# coronaampel_v2_fixed.net
KiCad netlist of a schematic drawn in EAGLE
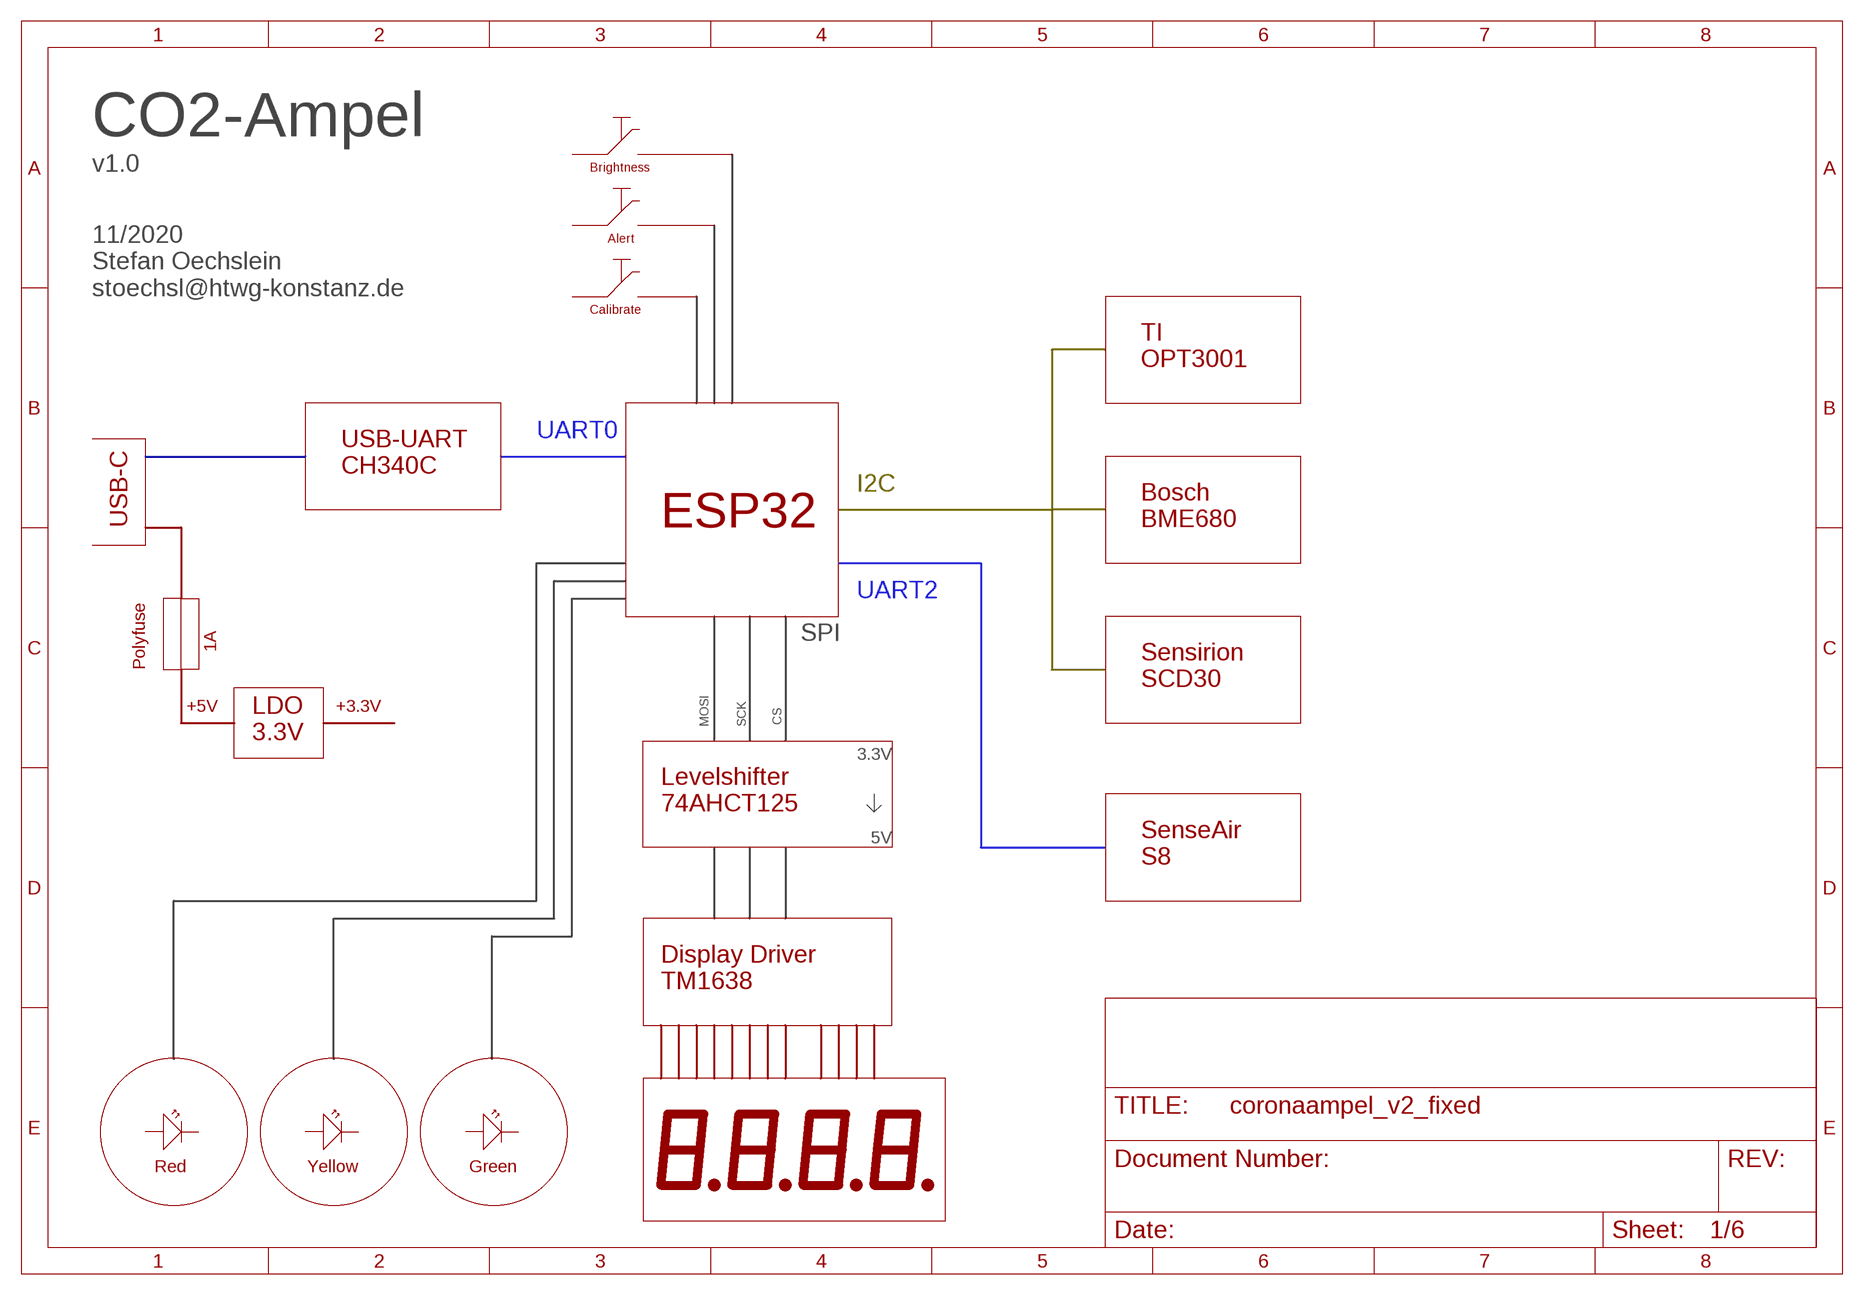
[diagram p0: schematic, sheet 1]
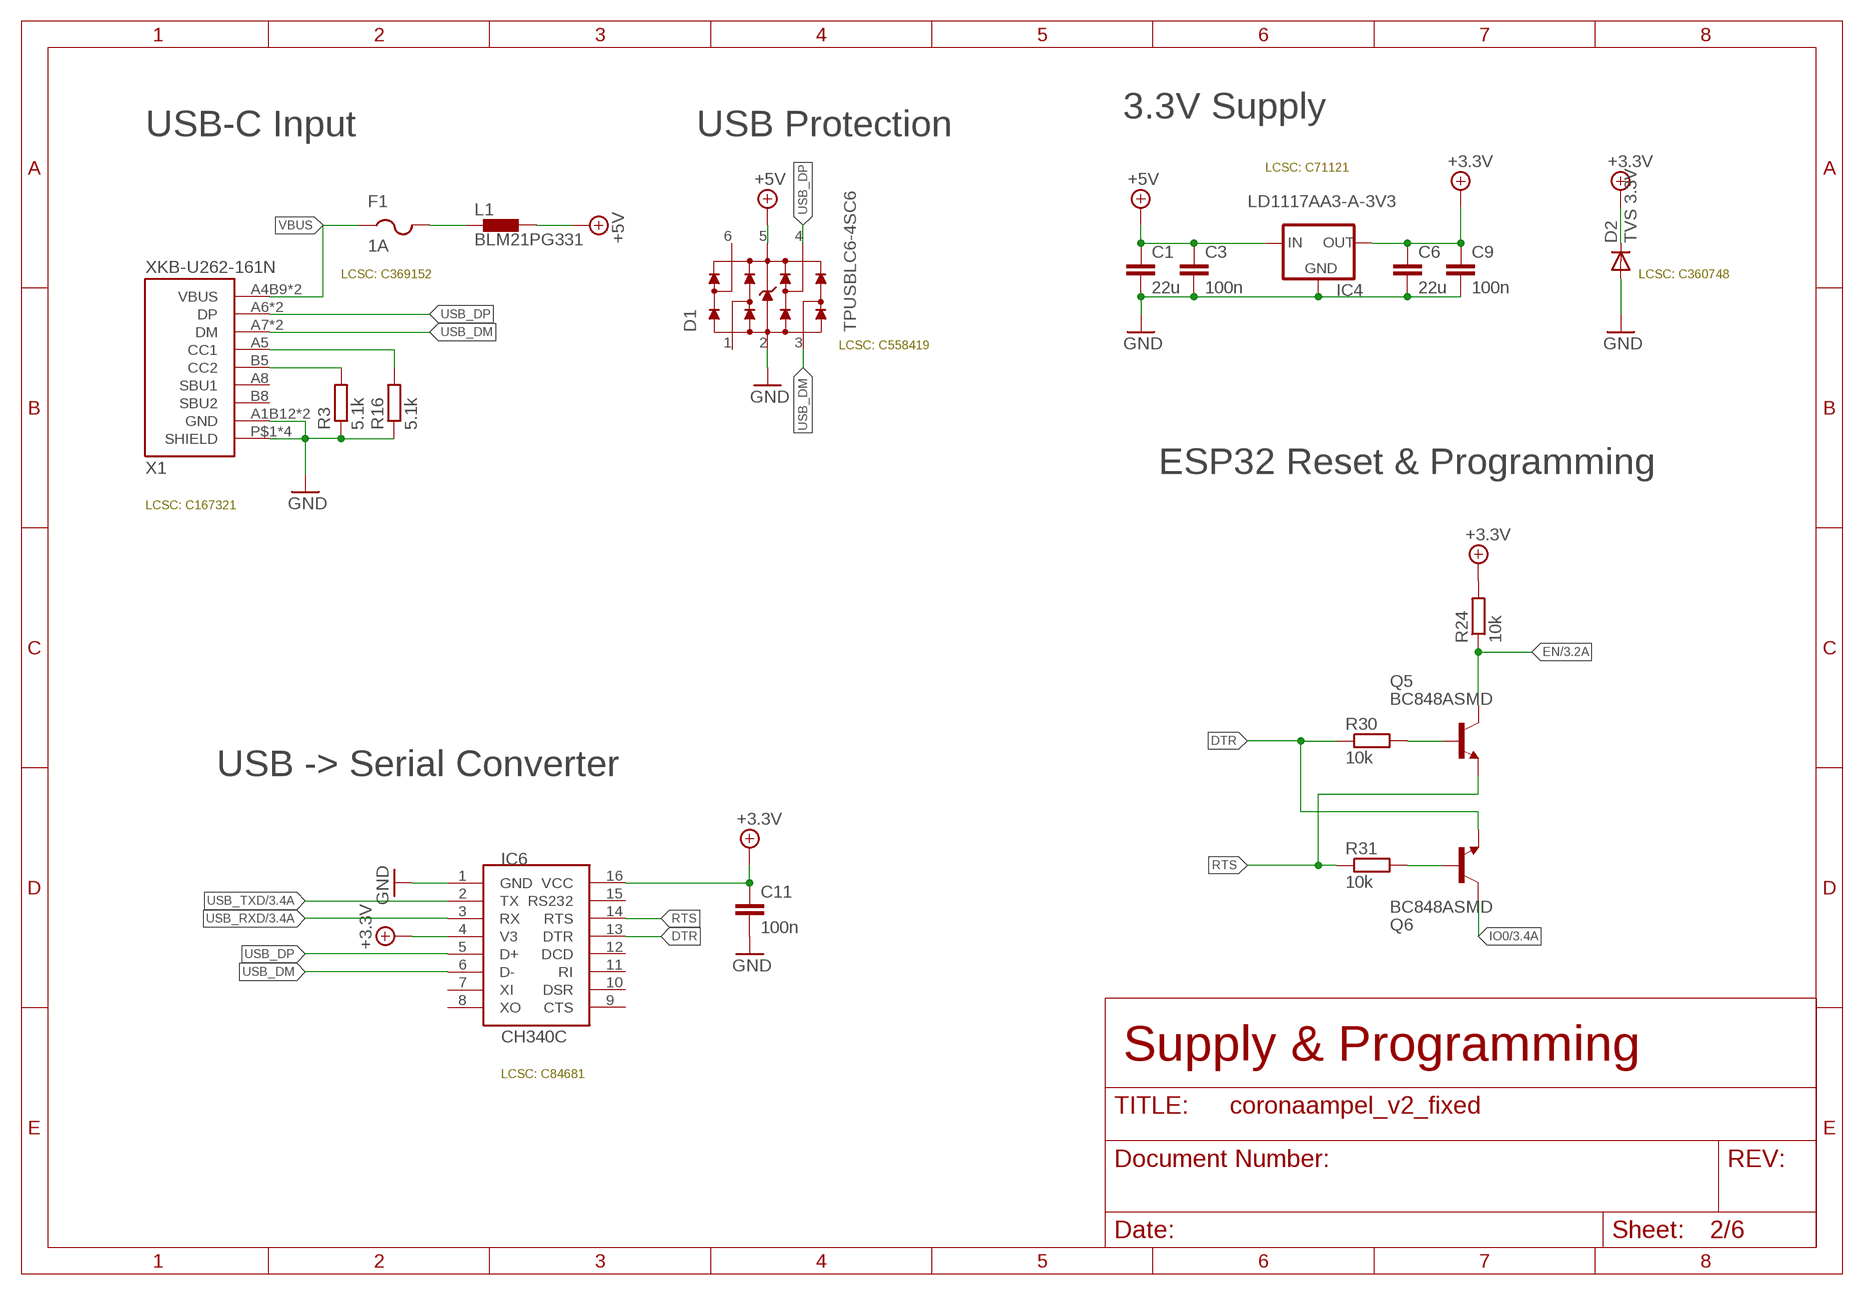
[diagram p1: schematic, sheet 2]
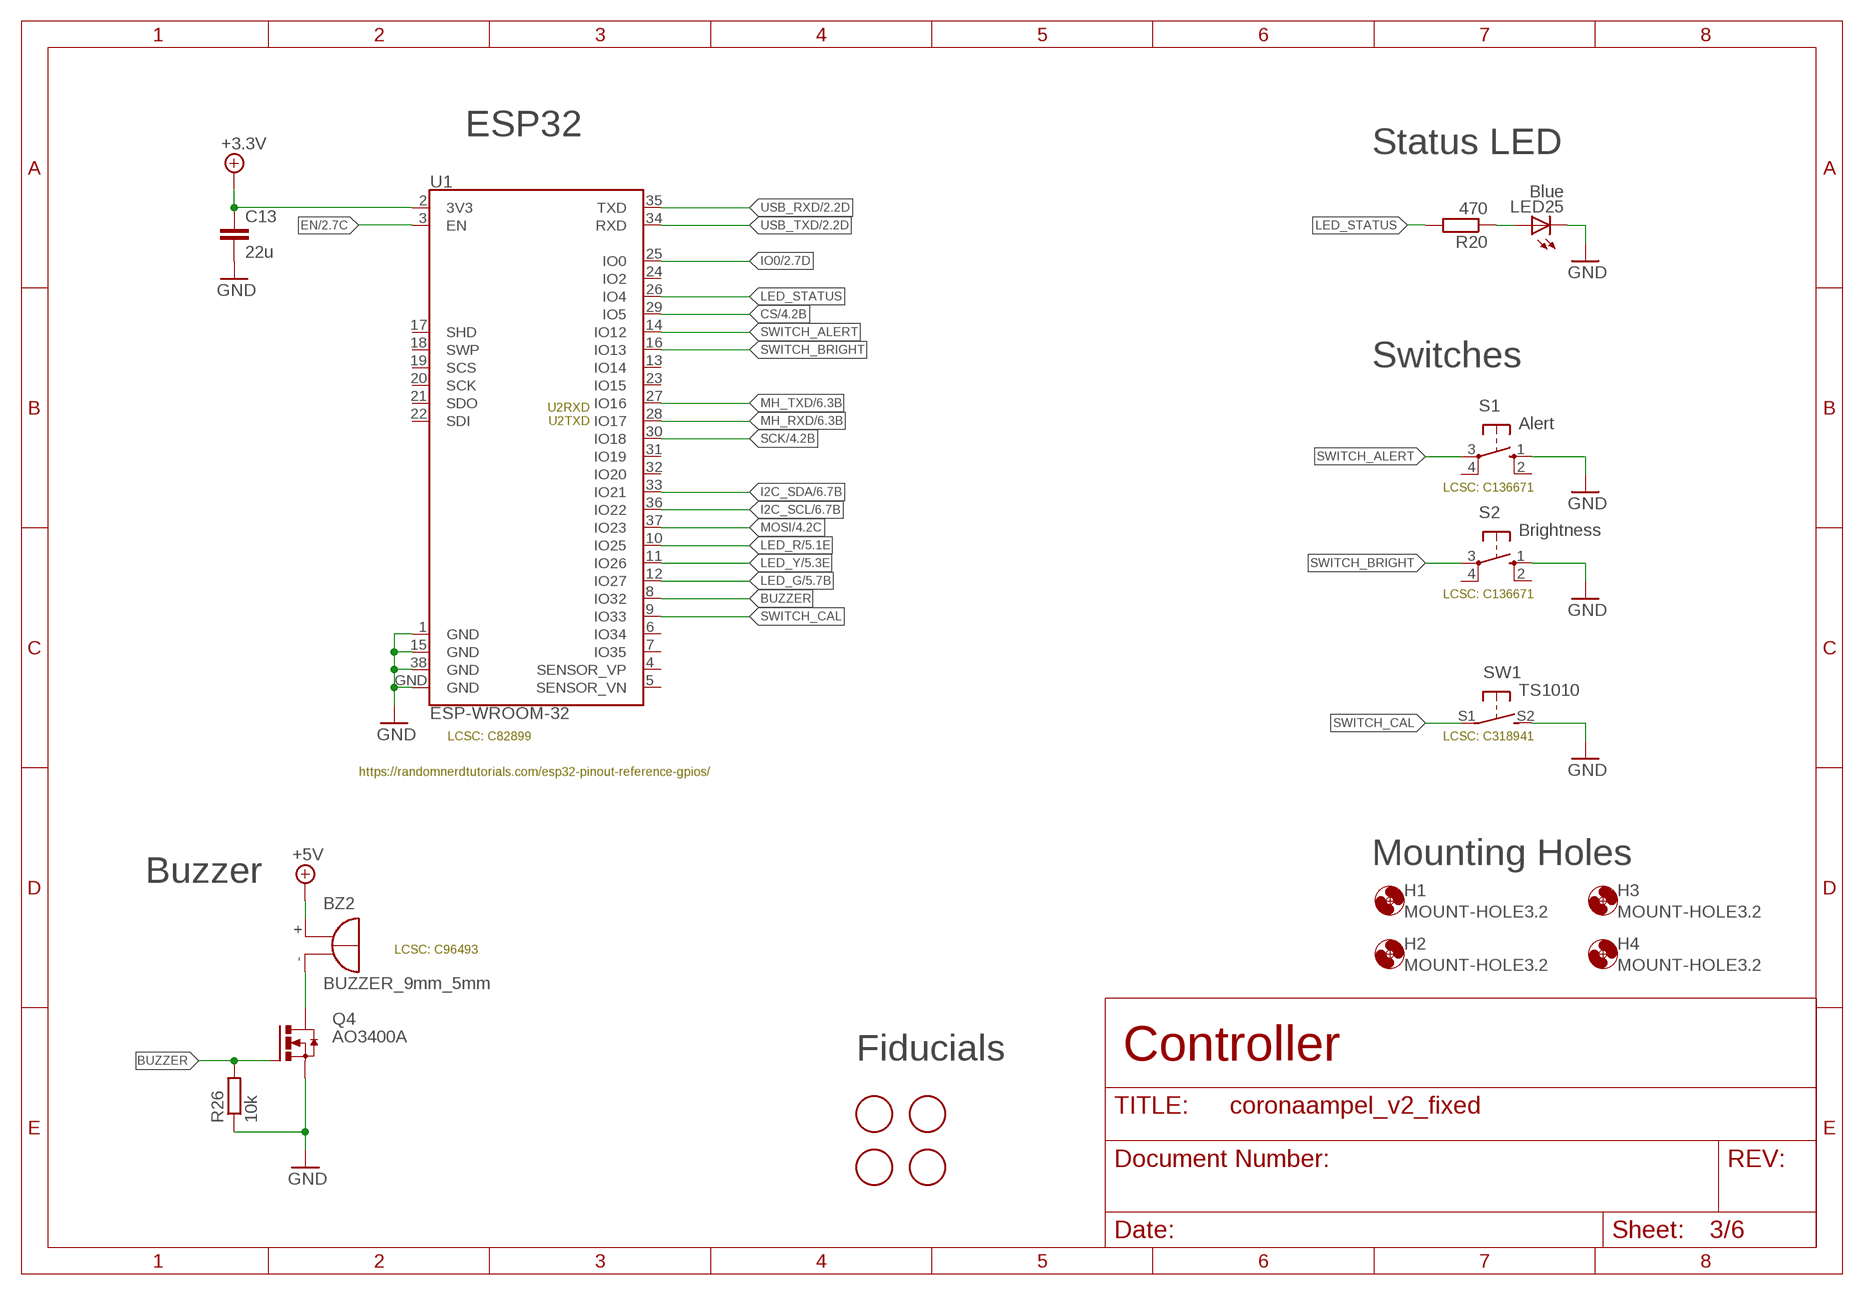
[diagram p2: schematic, sheet 3]
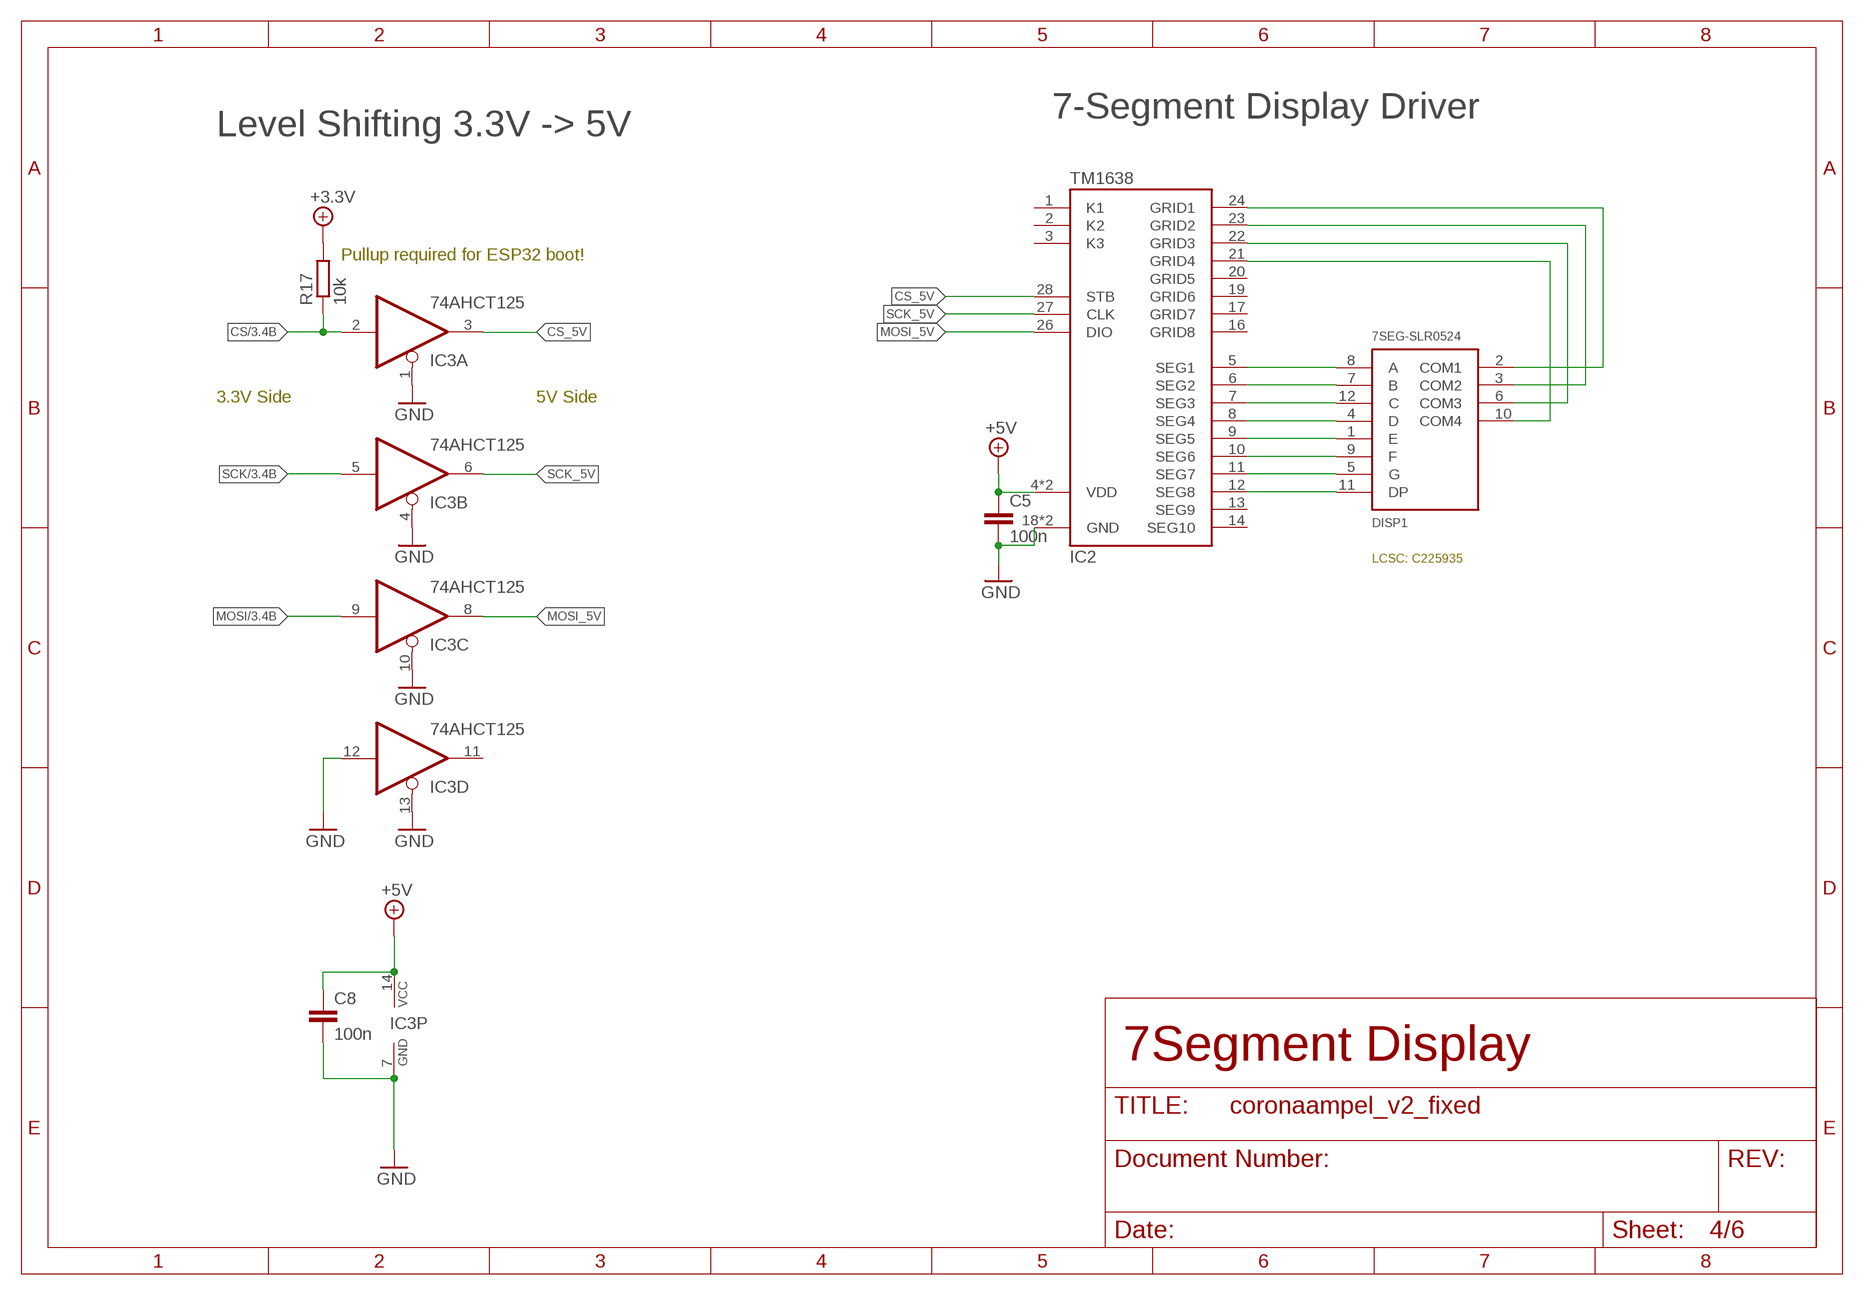
[diagram p3: schematic, sheet 4]
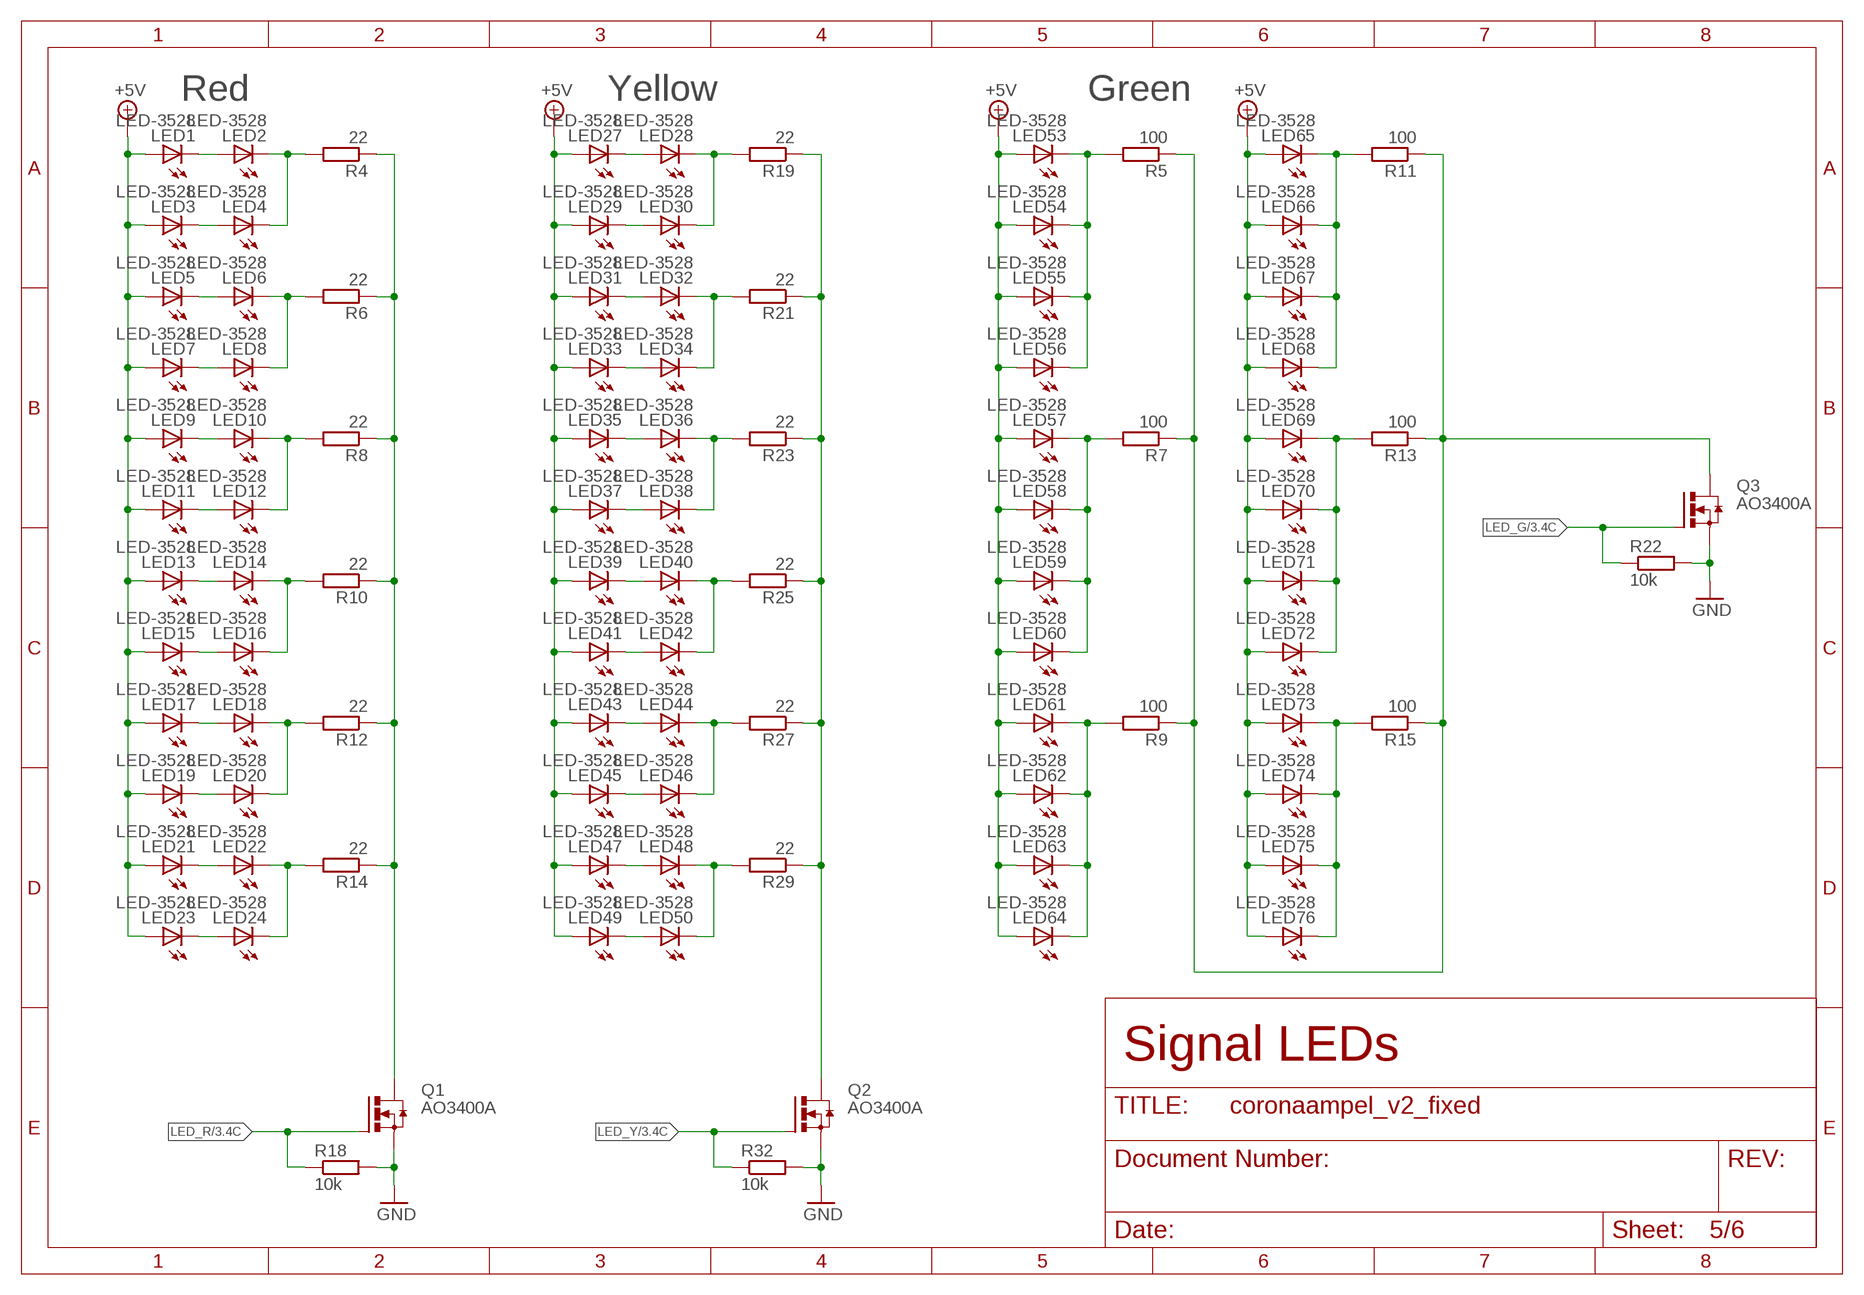
[diagram p4: schematic, sheet 5]
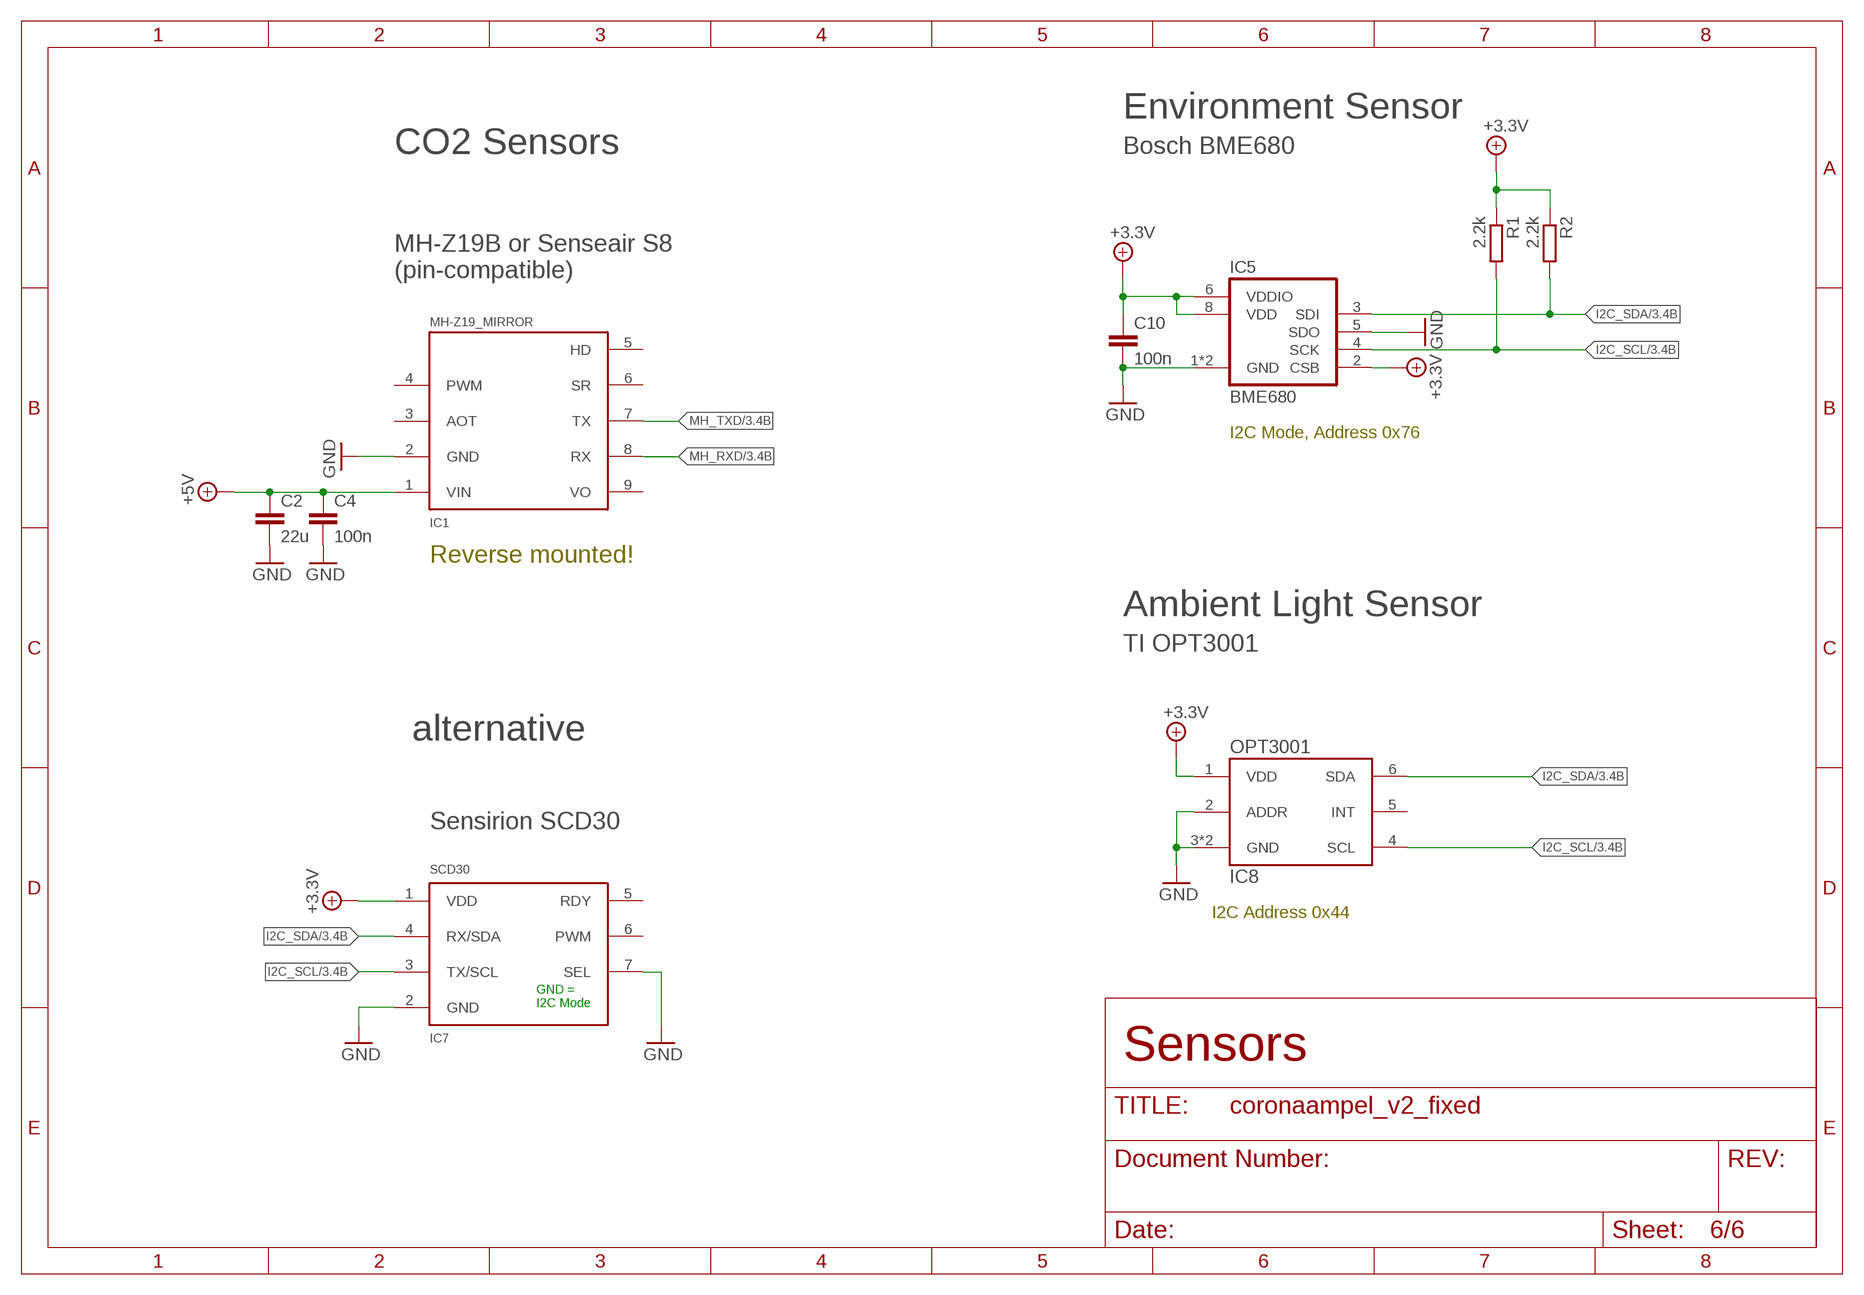
[diagram p5: schematic, sheet 6]

(export (version "E")
  (design (tool "Eeschema 10.0.6"))
  (components
    (comp (ref "C1")
      (value "22u")
      (footprint "eagle-import:C0805")
      (libsource (lib "eagle-import") (part "C-EUC0805"))
    )
    (comp (ref "C3")
      (value "100n")
      (footprint "eagle-import:C0805")
      (libsource (lib "eagle-import") (part "C-EUC0805"))
    )
    (comp (ref "C6")
      (value "22u")
      (footprint "eagle-import:C0805")
      (libsource (lib "eagle-import") (part "C-EUC0805"))
    )
    (comp (ref "C9")
      (value "100n")
      (footprint "eagle-import:C0805")
      (libsource (lib "eagle-import") (part "C-EUC0805"))
    )
    (comp (ref "C11")
      (value "100n")
      (footprint "eagle-import:C0805")
      (libsource (lib "eagle-import") (part "C-EUC0805"))
    )
    (comp (ref "D1")
      (value "TPUSBLC6-4SC6")
      (footprint "eagle-import:WE-TVS_SOT23-6L")
      (libsource (lib "eagle-import") (part "WE-TVS_824001"))
    )
    (comp (ref "D2")
      (value "TVS 3.3V")
      (footprint "eagle-import:SOD123")
      (libsource (lib "eagle-import") (part "DIODE-SOD123"))
    )
    (comp (ref "F1")
      (value "1A")
      (footprint "eagle-import:R0805")
      (libsource (lib "eagle-import") (part "PTCFUSE-0805"))
    )
    (comp (ref "IC4")
      (value "LD1117AA3-A-3V3")
      (footprint "eagle-import:SOT223")
      (libsource (lib "eagle-import") (part "LD1117AA3-A"))
    )
    (comp (ref "IC6")
      (value "CH340C")
      (footprint "eagle-import:SOIC16")
      (libsource (lib "eagle-import") (part "CH340G"))
    )
    (comp (ref "L1")
      (value "BLM21PG331")
      (footprint "eagle-import:0805")
      (libsource (lib "eagle-import") (part "BLM21PG331"))
    )
    (comp (ref "Q5")
      (value "BC848ASMD")
      (footprint "eagle-import:SOT23")
      (libsource (lib "eagle-import") (part "BC848SMDA"))
    )
    (comp (ref "Q6")
      (value "BC848ASMD")
      (footprint "eagle-import:SOT23")
      (libsource (lib "eagle-import") (part "BC848SMDA"))
    )
    (comp (ref "R3")
      (value "5.1k")
      (footprint "eagle-import:R0805")
      (libsource (lib "eagle-import") (part "R-EU_R0805"))
    )
    (comp (ref "R16")
      (value "5.1k")
      (footprint "eagle-import:R0805")
      (libsource (lib "eagle-import") (part "R-EU_R0805"))
    )
    (comp (ref "R24")
      (value "10k")
      (footprint "eagle-import:R0805")
      (libsource (lib "eagle-import") (part "R-EU_R0805"))
    )
    (comp (ref "R30")
      (value "10k")
      (footprint "eagle-import:R0805")
      (libsource (lib "eagle-import") (part "R-EU_R0805"))
    )
    (comp (ref "R31")
      (value "10k")
      (footprint "eagle-import:R0805")
      (libsource (lib "eagle-import") (part "R-EU_R0805"))
    )
    (comp (ref "X1")
      (value "XKB-U262-161N")
      (footprint "eagle-import:XKB_U262-161N")
      (libsource (lib "eagle-import") (part "XKB-U262-161N"))
    )
    (comp (ref "LED1")
      (value "LED-3528")
      (footprint "eagle-import:3528")
      (libsource (lib "eagle-import") (part "LED-3528"))
    )
    (comp (ref "LED2")
      (value "LED-3528")
      (footprint "eagle-import:3528")
      (libsource (lib "eagle-import") (part "LED-3528"))
    )
    (comp (ref "LED3")
      (value "LED-3528")
      (footprint "eagle-import:3528")
      (libsource (lib "eagle-import") (part "LED-3528"))
    )
    (comp (ref "LED4")
      (value "LED-3528")
      (footprint "eagle-import:3528")
      (libsource (lib "eagle-import") (part "LED-3528"))
    )
    (comp (ref "LED5")
      (value "LED-3528")
      (footprint "eagle-import:3528")
      (libsource (lib "eagle-import") (part "LED-3528"))
    )
    (comp (ref "LED6")
      (value "LED-3528")
      (footprint "eagle-import:3528")
      (libsource (lib "eagle-import") (part "LED-3528"))
    )
    (comp (ref "LED7")
      (value "LED-3528")
      (footprint "eagle-import:3528")
      (libsource (lib "eagle-import") (part "LED-3528"))
    )
    (comp (ref "LED8")
      (value "LED-3528")
      (footprint "eagle-import:3528")
      (libsource (lib "eagle-import") (part "LED-3528"))
    )
    (comp (ref "LED9")
      (value "LED-3528")
      (footprint "eagle-import:3528")
      (libsource (lib "eagle-import") (part "LED-3528"))
    )
    (comp (ref "LED10")
      (value "LED-3528")
      (footprint "eagle-import:3528")
      (libsource (lib "eagle-import") (part "LED-3528"))
    )
    (comp (ref "LED11")
      (value "LED-3528")
      (footprint "eagle-import:3528")
      (libsource (lib "eagle-import") (part "LED-3528"))
    )
    (comp (ref "LED12")
      (value "LED-3528")
      (footprint "eagle-import:3528")
      (libsource (lib "eagle-import") (part "LED-3528"))
    )
    (comp (ref "LED13")
      (value "LED-3528")
      (footprint "eagle-import:3528")
      (libsource (lib "eagle-import") (part "LED-3528"))
    )
    (comp (ref "LED14")
      (value "LED-3528")
      (footprint "eagle-import:3528")
      (libsource (lib "eagle-import") (part "LED-3528"))
    )
    (comp (ref "LED15")
      (value "LED-3528")
      (footprint "eagle-import:3528")
      (libsource (lib "eagle-import") (part "LED-3528"))
    )
    (comp (ref "LED16")
      (value "LED-3528")
      (footprint "eagle-import:3528")
      (libsource (lib "eagle-import") (part "LED-3528"))
    )
    (comp (ref "LED17")
      (value "LED-3528")
      (footprint "eagle-import:3528")
      (libsource (lib "eagle-import") (part "LED-3528"))
    )
    (comp (ref "LED18")
      (value "LED-3528")
      (footprint "eagle-import:3528")
      (libsource (lib "eagle-import") (part "LED-3528"))
    )
    (comp (ref "LED19")
      (value "LED-3528")
      (footprint "eagle-import:3528")
      (libsource (lib "eagle-import") (part "LED-3528"))
    )
    (comp (ref "LED20")
      (value "LED-3528")
      (footprint "eagle-import:3528")
      (libsource (lib "eagle-import") (part "LED-3528"))
    )
    (comp (ref "LED21")
      (value "LED-3528")
      (footprint "eagle-import:3528")
      (libsource (lib "eagle-import") (part "LED-3528"))
    )
    (comp (ref "LED22")
      (value "LED-3528")
      (footprint "eagle-import:3528")
      (libsource (lib "eagle-import") (part "LED-3528"))
    )
    (comp (ref "LED23")
      (value "LED-3528")
      (footprint "eagle-import:3528")
      (libsource (lib "eagle-import") (part "LED-3528"))
    )
    (comp (ref "LED24")
      (value "LED-3528")
      (footprint "eagle-import:3528")
      (libsource (lib "eagle-import") (part "LED-3528"))
    )
    (comp (ref "LED27")
      (value "LED-3528")
      (footprint "eagle-import:3528")
      (libsource (lib "eagle-import") (part "LED-3528"))
    )
    (comp (ref "LED28")
      (value "LED-3528")
      (footprint "eagle-import:3528")
      (libsource (lib "eagle-import") (part "LED-3528"))
    )
    (comp (ref "LED29")
      (value "LED-3528")
      (footprint "eagle-import:3528")
      (libsource (lib "eagle-import") (part "LED-3528"))
    )
    (comp (ref "LED30")
      (value "LED-3528")
      (footprint "eagle-import:3528")
      (libsource (lib "eagle-import") (part "LED-3528"))
    )
    (comp (ref "LED31")
      (value "LED-3528")
      (footprint "eagle-import:3528")
      (libsource (lib "eagle-import") (part "LED-3528"))
    )
    (comp (ref "LED32")
      (value "LED-3528")
      (footprint "eagle-import:3528")
      (libsource (lib "eagle-import") (part "LED-3528"))
    )
    (comp (ref "LED33")
      (value "LED-3528")
      (footprint "eagle-import:3528")
      (libsource (lib "eagle-import") (part "LED-3528"))
    )
    (comp (ref "LED34")
      (value "LED-3528")
      (footprint "eagle-import:3528")
      (libsource (lib "eagle-import") (part "LED-3528"))
    )
    (comp (ref "LED35")
      (value "LED-3528")
      (footprint "eagle-import:3528")
      (libsource (lib "eagle-import") (part "LED-3528"))
    )
    (comp (ref "LED36")
      (value "LED-3528")
      (footprint "eagle-import:3528")
      (libsource (lib "eagle-import") (part "LED-3528"))
    )
    (comp (ref "LED37")
      (value "LED-3528")
      (footprint "eagle-import:3528")
      (libsource (lib "eagle-import") (part "LED-3528"))
    )
    (comp (ref "LED38")
      (value "LED-3528")
      (footprint "eagle-import:3528")
      (libsource (lib "eagle-import") (part "LED-3528"))
    )
    (comp (ref "LED39")
      (value "LED-3528")
      (footprint "eagle-import:3528")
      (libsource (lib "eagle-import") (part "LED-3528"))
    )
    (comp (ref "LED40")
      (value "LED-3528")
      (footprint "eagle-import:3528")
      (libsource (lib "eagle-import") (part "LED-3528"))
    )
    (comp (ref "LED41")
      (value "LED-3528")
      (footprint "eagle-import:3528")
      (libsource (lib "eagle-import") (part "LED-3528"))
    )
    (comp (ref "LED42")
      (value "LED-3528")
      (footprint "eagle-import:3528")
      (libsource (lib "eagle-import") (part "LED-3528"))
    )
    (comp (ref "LED43")
      (value "LED-3528")
      (footprint "eagle-import:3528")
      (libsource (lib "eagle-import") (part "LED-3528"))
    )
    (comp (ref "LED44")
      (value "LED-3528")
      (footprint "eagle-import:3528")
      (libsource (lib "eagle-import") (part "LED-3528"))
    )
    (comp (ref "LED45")
      (value "LED-3528")
      (footprint "eagle-import:3528")
      (libsource (lib "eagle-import") (part "LED-3528"))
    )
    (comp (ref "LED46")
      (value "LED-3528")
      (footprint "eagle-import:3528")
      (libsource (lib "eagle-import") (part "LED-3528"))
    )
    (comp (ref "LED47")
      (value "LED-3528")
      (footprint "eagle-import:3528")
      (libsource (lib "eagle-import") (part "LED-3528"))
    )
    (comp (ref "LED48")
      (value "LED-3528")
      (footprint "eagle-import:3528")
      (libsource (lib "eagle-import") (part "LED-3528"))
    )
    (comp (ref "LED49")
      (value "LED-3528")
      (footprint "eagle-import:3528")
      (libsource (lib "eagle-import") (part "LED-3528"))
    )
    (comp (ref "LED50")
      (value "LED-3528")
      (footprint "eagle-import:3528")
      (libsource (lib "eagle-import") (part "LED-3528"))
    )
    (comp (ref "LED53")
      (value "LED-3528")
      (footprint "eagle-import:3528")
      (libsource (lib "eagle-import") (part "LED-3528"))
    )
    (comp (ref "LED54")
      (value "LED-3528")
      (footprint "eagle-import:3528")
      (libsource (lib "eagle-import") (part "LED-3528"))
    )
    (comp (ref "LED55")
      (value "LED-3528")
      (footprint "eagle-import:3528")
      (libsource (lib "eagle-import") (part "LED-3528"))
    )
    (comp (ref "LED56")
      (value "LED-3528")
      (footprint "eagle-import:3528")
      (libsource (lib "eagle-import") (part "LED-3528"))
    )
    (comp (ref "LED57")
      (value "LED-3528")
      (footprint "eagle-import:3528")
      (libsource (lib "eagle-import") (part "LED-3528"))
    )
    (comp (ref "LED58")
      (value "LED-3528")
      (footprint "eagle-import:3528")
      (libsource (lib "eagle-import") (part "LED-3528"))
    )
    (comp (ref "LED59")
      (value "LED-3528")
      (footprint "eagle-import:3528")
      (libsource (lib "eagle-import") (part "LED-3528"))
    )
    (comp (ref "LED60")
      (value "LED-3528")
      (footprint "eagle-import:3528")
      (libsource (lib "eagle-import") (part "LED-3528"))
    )
    (comp (ref "LED61")
      (value "LED-3528")
      (footprint "eagle-import:3528")
      (libsource (lib "eagle-import") (part "LED-3528"))
    )
    (comp (ref "LED62")
      (value "LED-3528")
      (footprint "eagle-import:3528")
      (libsource (lib "eagle-import") (part "LED-3528"))
    )
    (comp (ref "LED63")
      (value "LED-3528")
      (footprint "eagle-import:3528")
      (libsource (lib "eagle-import") (part "LED-3528"))
    )
    (comp (ref "LED64")
      (value "LED-3528")
      (footprint "eagle-import:3528")
      (libsource (lib "eagle-import") (part "LED-3528"))
    )
    (comp (ref "LED65")
      (value "LED-3528")
      (footprint "eagle-import:3528")
      (libsource (lib "eagle-import") (part "LED-3528"))
    )
    (comp (ref "LED66")
      (value "LED-3528")
      (footprint "eagle-import:3528")
      (libsource (lib "eagle-import") (part "LED-3528"))
    )
    (comp (ref "LED67")
      (value "LED-3528")
      (footprint "eagle-import:3528")
      (libsource (lib "eagle-import") (part "LED-3528"))
    )
    (comp (ref "LED68")
      (value "LED-3528")
      (footprint "eagle-import:3528")
      (libsource (lib "eagle-import") (part "LED-3528"))
    )
    (comp (ref "LED69")
      (value "LED-3528")
      (footprint "eagle-import:3528")
      (libsource (lib "eagle-import") (part "LED-3528"))
    )
    (comp (ref "LED70")
      (value "LED-3528")
      (footprint "eagle-import:3528")
      (libsource (lib "eagle-import") (part "LED-3528"))
    )
    (comp (ref "LED71")
      (value "LED-3528")
      (footprint "eagle-import:3528")
      (libsource (lib "eagle-import") (part "LED-3528"))
    )
    (comp (ref "LED72")
      (value "LED-3528")
      (footprint "eagle-import:3528")
      (libsource (lib "eagle-import") (part "LED-3528"))
    )
    (comp (ref "LED73")
      (value "LED-3528")
      (footprint "eagle-import:3528")
      (libsource (lib "eagle-import") (part "LED-3528"))
    )
    (comp (ref "LED74")
      (value "LED-3528")
      (footprint "eagle-import:3528")
      (libsource (lib "eagle-import") (part "LED-3528"))
    )
    (comp (ref "LED75")
      (value "LED-3528")
      (footprint "eagle-import:3528")
      (libsource (lib "eagle-import") (part "LED-3528"))
    )
    (comp (ref "LED76")
      (value "LED-3528")
      (footprint "eagle-import:3528")
      (libsource (lib "eagle-import") (part "LED-3528"))
    )
    (comp (ref "Q1")
      (value "AO3400A")
      (footprint "eagle-import:MICRO3")
      (libsource (lib "eagle-import") (part "IRLML2502"))
    )
    (comp (ref "Q2")
      (value "AO3400A")
      (footprint "eagle-import:MICRO3")
      (libsource (lib "eagle-import") (part "IRLML2502"))
    )
    (comp (ref "Q3")
      (value "AO3400A")
      (footprint "eagle-import:MICRO3")
      (libsource (lib "eagle-import") (part "IRLML2502"))
    )
    (comp (ref "R4")
      (value "22")
      (footprint "eagle-import:R0805")
      (libsource (lib "eagle-import") (part "R-EU_R0805"))
    )
    (comp (ref "R5")
      (value "100")
      (footprint "eagle-import:R0805")
      (libsource (lib "eagle-import") (part "R-EU_R0805"))
    )
    (comp (ref "R6")
      (value "22")
      (footprint "eagle-import:R0805")
      (libsource (lib "eagle-import") (part "R-EU_R0805"))
    )
    (comp (ref "R7")
      (value "100")
      (footprint "eagle-import:R0805")
      (libsource (lib "eagle-import") (part "R-EU_R0805"))
    )
    (comp (ref "R8")
      (value "22")
      (footprint "eagle-import:R0805")
      (libsource (lib "eagle-import") (part "R-EU_R0805"))
    )
    (comp (ref "R9")
      (value "100")
      (footprint "eagle-import:R0805")
      (libsource (lib "eagle-import") (part "R-EU_R0805"))
    )
    (comp (ref "R10")
      (value "22")
      (footprint "eagle-import:R0805")
      (libsource (lib "eagle-import") (part "R-EU_R0805"))
    )
    (comp (ref "R11")
      (value "100")
      (footprint "eagle-import:R0805")
      (libsource (lib "eagle-import") (part "R-EU_R0805"))
    )
    (comp (ref "R12")
      (value "22")
      (footprint "eagle-import:R0805")
      (libsource (lib "eagle-import") (part "R-EU_R0805"))
    )
    (comp (ref "R13")
      (value "100")
      (footprint "eagle-import:R0805")
      (libsource (lib "eagle-import") (part "R-EU_R0805"))
    )
    (comp (ref "R14")
      (value "22")
      (footprint "eagle-import:R0805")
      (libsource (lib "eagle-import") (part "R-EU_R0805"))
    )
    (comp (ref "R15")
      (value "100")
      (footprint "eagle-import:R0805")
      (libsource (lib "eagle-import") (part "R-EU_R0805"))
    )
    (comp (ref "R18")
      (value "10k")
      (footprint "eagle-import:R0805")
      (libsource (lib "eagle-import") (part "R-EU_R0805"))
    )
    (comp (ref "R19")
      (value "22")
      (footprint "eagle-import:R0805")
      (libsource (lib "eagle-import") (part "R-EU_R0805"))
    )
    (comp (ref "R21")
      (value "22")
      (footprint "eagle-import:R0805")
      (libsource (lib "eagle-import") (part "R-EU_R0805"))
    )
    (comp (ref "R22")
      (value "10k")
      (footprint "eagle-import:R0805")
      (libsource (lib "eagle-import") (part "R-EU_R0805"))
    )
    (comp (ref "R23")
      (value "22")
      (footprint "eagle-import:R0805")
      (libsource (lib "eagle-import") (part "R-EU_R0805"))
    )
    (comp (ref "R25")
      (value "22")
      (footprint "eagle-import:R0805")
      (libsource (lib "eagle-import") (part "R-EU_R0805"))
    )
    (comp (ref "R27")
      (value "22")
      (footprint "eagle-import:R0805")
      (libsource (lib "eagle-import") (part "R-EU_R0805"))
    )
    (comp (ref "R29")
      (value "22")
      (footprint "eagle-import:R0805")
      (libsource (lib "eagle-import") (part "R-EU_R0805"))
    )
    (comp (ref "R32")
      (value "10k")
      (footprint "eagle-import:R0805")
      (libsource (lib "eagle-import") (part "R-EU_R0805"))
    )
    (comp (ref "C5")
      (value "100n")
      (footprint "eagle-import:C0805")
      (libsource (lib "eagle-import") (part "C-EUC0805"))
    )
    (comp (ref "C8")
      (value "100n")
      (footprint "eagle-import:C0805")
      (libsource (lib "eagle-import") (part "C-EUC0805"))
    )
    (comp (ref "DISP1")
      (value "7SEG-SLR0524")
      (footprint "eagle-import:SEG-SLR0524")
      (libsource (lib "eagle-import") (part "7SEG-SLR0524"))
    )
    (comp (ref "IC2")
      (value "TM1638")
      (footprint "eagle-import:SO-28L")
      (libsource (lib "eagle-import") (part "TM1638"))
    )
    (comp (ref "IC3")
      (value "74AHCT125")
      (footprint "eagle-import:TSSOP14")
      (libsource (lib "eagle-import") (part "74125PWABT"))
    )
    (comp (ref "R17")
      (value "10k")
      (footprint "eagle-import:R0805")
      (libsource (lib "eagle-import") (part "R-EU_R0805"))
    )
    (comp (ref "C2")
      (value "22u")
      (footprint "eagle-import:C0805")
      (libsource (lib "eagle-import") (part "C-EUC0805"))
    )
    (comp (ref "C4")
      (value "100n")
      (footprint "eagle-import:C0805")
      (libsource (lib "eagle-import") (part "C-EUC0805"))
    )
    (comp (ref "C10")
      (value "100n")
      (footprint "eagle-import:C0805")
      (libsource (lib "eagle-import") (part "C-EUC0805"))
    )
    (comp (ref "IC1")
      (value "MH-Z19_MIRROR")
      (footprint "eagle-import:MH-Z19_MIRROR")
      (libsource (lib "eagle-import") (part "MH-Z19_MIRROR"))
    )
    (comp (ref "IC5")
      (value "BME680")
      (footprint "eagle-import:BME680")
      (libsource (lib "eagle-import") (part "BME680"))
    )
    (comp (ref "IC7")
      (value "SCD30")
      (footprint "eagle-import:SCD30")
      (libsource (lib "eagle-import") (part "SCD30"))
    )
    (comp (ref "IC8")
      (value "OPT3001")
      (footprint "eagle-import:USON6")
      (libsource (lib "eagle-import") (part "OPT3001"))
    )
    (comp (ref "R1")
      (value "2.2k")
      (footprint "eagle-import:R0805")
      (libsource (lib "eagle-import") (part "R-EU_R0805"))
    )
    (comp (ref "R2")
      (value "2.2k")
      (footprint "eagle-import:R0805")
      (libsource (lib "eagle-import") (part "R-EU_R0805"))
    )
    (comp (ref "BZ2")
      (value "BUZZER_9mm_5mm")
      (footprint "eagle-import:BUZ_9_5")
      (libsource (lib "eagle-import") (part "BUZ_9_5"))
    )
    (comp (ref "C13")
      (value "22u")
      (footprint "eagle-import:C0805")
      (libsource (lib "eagle-import") (part "C-EUC0805"))
    )
    (comp (ref "H1")
      (value "MOUNT-HOLE3.2")
      (footprint "eagle-import:3,2")
      (libsource (lib "eagle-import") (part "MOUNT-HOLE3.2"))
    )
    (comp (ref "H2")
      (value "MOUNT-HOLE3.2")
      (footprint "eagle-import:3,2")
      (libsource (lib "eagle-import") (part "MOUNT-HOLE3.2"))
    )
    (comp (ref "H3")
      (value "MOUNT-HOLE3.2")
      (footprint "eagle-import:3,2")
      (libsource (lib "eagle-import") (part "MOUNT-HOLE3.2"))
    )
    (comp (ref "H4")
      (value "MOUNT-HOLE3.2")
      (footprint "eagle-import:3,2")
      (libsource (lib "eagle-import") (part "MOUNT-HOLE3.2"))
    )
    (comp (ref "LED25")
      (value "Blue")
      (footprint "eagle-import:CHIPLED_0805")
      (libsource (lib "eagle-import") (part "LEDCHIPLED_0805"))
    )
    (comp (ref "Q4")
      (value "AO3400A")
      (footprint "eagle-import:MICRO3")
      (libsource (lib "eagle-import") (part "IRLML2502"))
    )
    (comp (ref "R20")
      (value "470")
      (footprint "eagle-import:R0805")
      (libsource (lib "eagle-import") (part "R-EU_R0805"))
    )
    (comp (ref "R26")
      (value "10k")
      (footprint "eagle-import:R0805")
      (libsource (lib "eagle-import") (part "R-EU_R0805"))
    )
    (comp (ref "S1")
      (value "Alert")
      (footprint "eagle-import:B3F-10XX")
      (fields (field (name "MPN") "B3F-1000"))
      (libsource (lib "eagle-import") (part "10-XX"))
    )
    (comp (ref "S2")
      (value "Brightness")
      (footprint "eagle-import:B3F-10XX")
      (fields (field (name "MPN") "B3F-1000"))
      (libsource (lib "eagle-import") (part "10-XX"))
    )
    (comp (ref "SW1")
      (value "TS1010")
      (footprint "eagle-import:TS1010")
      (libsource (lib "eagle-import") (part "TS1010"))
    )
    (comp (ref "U$4")
      (value "FIDUCIAL")
      (footprint "eagle-import:FIDUCIAL_1MM")
      (libsource (lib "eagle-import") (part "FIDUCIAL"))
    )
    (comp (ref "U$6")
      (value "FIDUCIAL")
      (footprint "eagle-import:FIDUCIAL_1MM")
      (libsource (lib "eagle-import") (part "FIDUCIAL"))
    )
    (comp (ref "U$7")
      (value "FIDUCIAL")
      (footprint "eagle-import:FIDUCIAL_1MM")
      (libsource (lib "eagle-import") (part "FIDUCIAL"))
    )
    (comp (ref "U$8")
      (value "FIDUCIAL")
      (footprint "eagle-import:FIDUCIAL_1MM")
      (libsource (lib "eagle-import") (part "FIDUCIAL"))
    )
    (comp (ref "U1")
      (value "ESP-WROOM-32")
      (footprint "eagle-import:ESP-WROOM-32")
      (libsource (lib "eagle-import") (part "ESP-WROOM-32"))
    )
  )
  (nets
    (net (code "1") (name "+3,3V") (class "Default")
      (node (ref "C10") (pin "1") (pinfunction "1_1") (pintype "passive"))
      (node (ref "C11") (pin "1") (pinfunction "1_1") (pintype "passive"))
      (node (ref "C13") (pin "1") (pinfunction "1_1") (pintype "passive"))
      (node (ref "C6") (pin "1") (pinfunction "1_1") (pintype "passive"))
      (node (ref "C9") (pin "1") (pinfunction "1_1") (pintype "passive"))
      (node (ref "D2") (pin "C") (pinfunction "C_C") (pintype "passive"))
      (node (ref "IC4") (pin "2") (pinfunction "OUT_2") (pintype "passive"))
      (node (ref "IC4") (pin "4") (pinfunction "OUT_4") (pintype "passive"))
      (node (ref "IC5") (pin "2") (pinfunction "CSB_2") (pintype "input"))
      (node (ref "IC5") (pin "6") (pinfunction "VDDIO_6") (pintype "power_in"))
      (node (ref "IC5") (pin "8") (pinfunction "VDD_8") (pintype "power_in"))
      (node (ref "IC6") (pin "16") (pinfunction "VCC_16") (pintype "bidirectional"))
      (node (ref "IC6") (pin "4") (pinfunction "V3_4") (pintype "bidirectional"))
      (node (ref "IC7") (pin "1") (pinfunction "VDD_1") (pintype "bidirectional"))
      (node (ref "IC8") (pin "1") (pinfunction "VDD_1") (pintype "bidirectional"))
      (node (ref "R1") (pin "1") (pinfunction "1_1") (pintype "passive"))
      (node (ref "R17") (pin "2") (pinfunction "2_2") (pintype "passive"))
      (node (ref "R2") (pin "1") (pinfunction "1_1") (pintype "passive"))
      (node (ref "R24") (pin "2") (pinfunction "2_2") (pintype "passive"))
      (node (ref "U1") (pin "2") (pinfunction "3V3_2") (pintype "bidirectional"))
    )
    (net (code "2") (name "+5V") (class "Default")
      (node (ref "BZ2") (pin "+") (pinfunction "+_+") (pintype "passive"))
      (node (ref "C1") (pin "1") (pinfunction "1_1") (pintype "passive"))
      (node (ref "C2") (pin "1") (pinfunction "1_1") (pintype "passive"))
      (node (ref "C3") (pin "1") (pinfunction "1_1") (pintype "passive"))
      (node (ref "C4") (pin "1") (pinfunction "1_1") (pintype "passive"))
      (node (ref "C5") (pin "1") (pinfunction "1_1") (pintype "passive"))
      (node (ref "C8") (pin "1") (pinfunction "1_1") (pintype "passive"))
      (node (ref "D1") (pin "5") (pinfunction "VDD_5") (pintype "power_in"))
      (node (ref "IC1") (pin "1") (pinfunction "VIN_1") (pintype "bidirectional"))
      (node (ref "IC2") (pin "15") (pinfunction "VDD_15") (pintype "bidirectional"))
      (node (ref "IC2") (pin "4") (pinfunction "VDD_4") (pintype "bidirectional"))
      (node (ref "IC3") (pin "14") (pinfunction "VCC_14") (pintype "power_in"))
      (node (ref "IC4") (pin "3") (pinfunction "IN_3") (pintype "input"))
      (node (ref "L1") (pin "2") (pinfunction "2_2") (pintype "passive"))
      (node (ref "LED1") (pin "A") (pinfunction "A_A") (pintype "passive"))
      (node (ref "LED11") (pin "A") (pinfunction "A_A") (pintype "passive"))
      (node (ref "LED13") (pin "A") (pinfunction "A_A") (pintype "passive"))
      (node (ref "LED15") (pin "A") (pinfunction "A_A") (pintype "passive"))
      (node (ref "LED17") (pin "A") (pinfunction "A_A") (pintype "passive"))
      (node (ref "LED19") (pin "A") (pinfunction "A_A") (pintype "passive"))
      (node (ref "LED21") (pin "A") (pinfunction "A_A") (pintype "passive"))
      (node (ref "LED23") (pin "A") (pinfunction "A_A") (pintype "passive"))
      (node (ref "LED27") (pin "A") (pinfunction "A_A") (pintype "passive"))
      (node (ref "LED29") (pin "A") (pinfunction "A_A") (pintype "passive"))
      (node (ref "LED3") (pin "A") (pinfunction "A_A") (pintype "passive"))
      (node (ref "LED31") (pin "A") (pinfunction "A_A") (pintype "passive"))
      (node (ref "LED33") (pin "A") (pinfunction "A_A") (pintype "passive"))
      (node (ref "LED35") (pin "A") (pinfunction "A_A") (pintype "passive"))
      (node (ref "LED37") (pin "A") (pinfunction "A_A") (pintype "passive"))
      (node (ref "LED39") (pin "A") (pinfunction "A_A") (pintype "passive"))
      (node (ref "LED41") (pin "A") (pinfunction "A_A") (pintype "passive"))
      (node (ref "LED43") (pin "A") (pinfunction "A_A") (pintype "passive"))
      (node (ref "LED45") (pin "A") (pinfunction "A_A") (pintype "passive"))
      (node (ref "LED47") (pin "A") (pinfunction "A_A") (pintype "passive"))
      (node (ref "LED49") (pin "A") (pinfunction "A_A") (pintype "passive"))
      (node (ref "LED5") (pin "A") (pinfunction "A_A") (pintype "passive"))
      (node (ref "LED53") (pin "A") (pinfunction "A_A") (pintype "passive"))
      (node (ref "LED54") (pin "A") (pinfunction "A_A") (pintype "passive"))
      (node (ref "LED55") (pin "A") (pinfunction "A_A") (pintype "passive"))
      (node (ref "LED56") (pin "A") (pinfunction "A_A") (pintype "passive"))
      (node (ref "LED57") (pin "A") (pinfunction "A_A") (pintype "passive"))
      (node (ref "LED58") (pin "A") (pinfunction "A_A") (pintype "passive"))
      (node (ref "LED59") (pin "A") (pinfunction "A_A") (pintype "passive"))
      (node (ref "LED60") (pin "A") (pinfunction "A_A") (pintype "passive"))
      (node (ref "LED61") (pin "A") (pinfunction "A_A") (pintype "passive"))
      (node (ref "LED62") (pin "A") (pinfunction "A_A") (pintype "passive"))
      (node (ref "LED63") (pin "A") (pinfunction "A_A") (pintype "passive"))
      (node (ref "LED64") (pin "A") (pinfunction "A_A") (pintype "passive"))
      (node (ref "LED65") (pin "A") (pinfunction "A_A") (pintype "passive"))
      (node (ref "LED66") (pin "A") (pinfunction "A_A") (pintype "passive"))
      (node (ref "LED67") (pin "A") (pinfunction "A_A") (pintype "passive"))
      (node (ref "LED68") (pin "A") (pinfunction "A_A") (pintype "passive"))
      (node (ref "LED69") (pin "A") (pinfunction "A_A") (pintype "passive"))
      (node (ref "LED7") (pin "A") (pinfunction "A_A") (pintype "passive"))
      (node (ref "LED70") (pin "A") (pinfunction "A_A") (pintype "passive"))
      (node (ref "LED71") (pin "A") (pinfunction "A_A") (pintype "passive"))
      (node (ref "LED72") (pin "A") (pinfunction "A_A") (pintype "passive"))
      (node (ref "LED73") (pin "A") (pinfunction "A_A") (pintype "passive"))
      (node (ref "LED74") (pin "A") (pinfunction "A_A") (pintype "passive"))
      (node (ref "LED75") (pin "A") (pinfunction "A_A") (pintype "passive"))
      (node (ref "LED76") (pin "A") (pinfunction "A_A") (pintype "passive"))
      (node (ref "LED9") (pin "A") (pinfunction "A_A") (pintype "passive"))
    )
    (net (code "3") (name "BUZZER") (class "Default")
      (node (ref "Q4") (pin "1") (pinfunction "G_1") (pintype "passive"))
      (node (ref "R26") (pin "2") (pinfunction "2_2") (pintype "passive"))
      (node (ref "U1") (pin "8") (pinfunction "IO32_8") (pintype "bidirectional"))
    )
    (net (code "4") (name "CS") (class "Default")
      (node (ref "IC3") (pin "2") (pinfunction "I_2") (pintype "input"))
      (node (ref "R17") (pin "1") (pinfunction "1_1") (pintype "passive"))
      (node (ref "U1") (pin "29") (pinfunction "IO5_29") (pintype "bidirectional"))
    )
    (net (code "5") (name "CS_5V") (class "Default")
      (node (ref "IC2") (pin "28") (pinfunction "STB_28") (pintype "bidirectional"))
      (node (ref "IC3") (pin "3") (pinfunction "O_3") (pintype "tri_state"))
    )
    (net (code "6") (name "DTR") (class "Default")
      (node (ref "IC6") (pin "13") (pinfunction "DTR_13") (pintype "bidirectional"))
      (node (ref "Q6") (pin "2") (pinfunction "E_2") (pintype "passive"))
      (node (ref "R30") (pin "1") (pinfunction "1_1") (pintype "passive"))
    )
    (net (code "7") (name "EN") (class "Default")
      (node (ref "Q5") (pin "3") (pinfunction "C_3") (pintype "passive"))
      (node (ref "R24") (pin "1") (pinfunction "1_1") (pintype "passive"))
      (node (ref "U1") (pin "3") (pinfunction "EN_3") (pintype "bidirectional"))
    )
    (net (code "8") (name "GND") (class "Default")
      (node (ref "C1") (pin "2") (pinfunction "2_2") (pintype "passive"))
      (node (ref "C10") (pin "2") (pinfunction "2_2") (pintype "passive"))
      (node (ref "C11") (pin "2") (pinfunction "2_2") (pintype "passive"))
      (node (ref "C13") (pin "2") (pinfunction "2_2") (pintype "passive"))
      (node (ref "C2") (pin "2") (pinfunction "2_2") (pintype "passive"))
      (node (ref "C3") (pin "2") (pinfunction "2_2") (pintype "passive"))
      (node (ref "C4") (pin "2") (pinfunction "2_2") (pintype "passive"))
      (node (ref "C5") (pin "2") (pinfunction "2_2") (pintype "passive"))
      (node (ref "C6") (pin "2") (pinfunction "2_2") (pintype "passive"))
      (node (ref "C8") (pin "2") (pinfunction "2_2") (pintype "passive"))
      (node (ref "C9") (pin "2") (pinfunction "2_2") (pintype "passive"))
      (node (ref "D1") (pin "2") (pinfunction "GND_2") (pintype "power_in"))
      (node (ref "D2") (pin "A") (pinfunction "A_A") (pintype "passive"))
      (node (ref "IC1") (pin "2") (pinfunction "GND_2") (pintype "bidirectional"))
      (node (ref "IC2") (pin "18") (pinfunction "GND_18") (pintype "bidirectional"))
      (node (ref "IC2") (pin "25") (pinfunction "GND_25") (pintype "bidirectional"))
      (node (ref "IC3") (pin "1") (pinfunction "OE_1") (pintype "input"))
      (node (ref "IC3") (pin "10") (pinfunction "OE_10") (pintype "input"))
      (node (ref "IC3") (pin "12") (pinfunction "I_12") (pintype "input"))
      (node (ref "IC3") (pin "13") (pinfunction "OE_13") (pintype "input"))
      (node (ref "IC3") (pin "4") (pinfunction "OE_4") (pintype "input"))
      (node (ref "IC3") (pin "7") (pinfunction "GND_7") (pintype "power_in"))
      (node (ref "IC4") (pin "1") (pinfunction "GND_1") (pintype "input"))
      (node (ref "IC5") (pin "1") (pinfunction "GND_1") (pintype "power_in"))
      (node (ref "IC5") (pin "5") (pinfunction "SDO_5") (pintype "output"))
      (node (ref "IC5") (pin "7") (pinfunction "GND_7") (pintype "power_in"))
      (node (ref "IC6") (pin "1") (pinfunction "GND_1") (pintype "bidirectional"))
      (node (ref "IC7") (pin "2") (pinfunction "GND_2") (pintype "bidirectional"))
      (node (ref "IC7") (pin "7") (pinfunction "SEL_7") (pintype "bidirectional"))
      (node (ref "IC8") (pin "2") (pinfunction "ADDR_2") (pintype "bidirectional"))
      (node (ref "IC8") (pin "3") (pinfunction "GND_3") (pintype "bidirectional"))
      (node (ref "IC8") (pin "EP") (pinfunction "GND_EP") (pintype "bidirectional"))
      (node (ref "LED25") (pin "C") (pinfunction "C_C") (pintype "passive"))
      (node (ref "Q1") (pin "2") (pinfunction "S_2") (pintype "passive"))
      (node (ref "Q2") (pin "2") (pinfunction "S_2") (pintype "passive"))
      (node (ref "Q3") (pin "2") (pinfunction "S_2") (pintype "passive"))
      (node (ref "Q4") (pin "2") (pinfunction "S_2") (pintype "passive"))
      (node (ref "R16") (pin "1") (pinfunction "1_1") (pintype "passive"))
      (node (ref "R18") (pin "2") (pinfunction "2_2") (pintype "passive"))
      (node (ref "R22") (pin "2") (pinfunction "2_2") (pintype "passive"))
      (node (ref "R26") (pin "1") (pinfunction "1_1") (pintype "passive"))
      (node (ref "R3") (pin "1") (pinfunction "1_1") (pintype "passive"))
      (node (ref "R32") (pin "2") (pinfunction "2_2") (pintype "passive"))
      (node (ref "S1") (pin "1") (pinfunction "S_1") (pintype "passive"))
      (node (ref "S2") (pin "1") (pinfunction "S_1") (pintype "passive"))
      (node (ref "SW1") (pin "S2") (pinfunction "S_S2") (pintype "passive"))
      (node (ref "U1") (pin "1") (pinfunction "GND_1") (pintype "bidirectional"))
      (node (ref "U1") (pin "15") (pinfunction "GND_15") (pintype "bidirectional"))
      (node (ref "U1") (pin "38") (pinfunction "GND_38") (pintype "bidirectional"))
      (node (ref "U1") (pin "GND") (pinfunction "GND_GND") (pintype "bidirectional"))
      (node (ref "X1") (pin "A1B12") (pinfunction "GND_A1B12") (pintype "bidirectional"))
      (node (ref "X1") (pin "B1A12") (pinfunction "GND_B1A12") (pintype "bidirectional"))
      (node (ref "X1") (pin "P$1") (pinfunction "SHIELD_P$1") (pintype "bidirectional"))
      (node (ref "X1") (pin "P$2") (pinfunction "SHIELD_P$2") (pintype "bidirectional"))
      (node (ref "X1") (pin "P$3") (pinfunction "SHIELD_P$3") (pintype "bidirectional"))
      (node (ref "X1") (pin "P$4") (pinfunction "SHIELD_P$4") (pintype "bidirectional"))
    )
    (net (code "9") (name "I2C_SCL") (class "Default")
      (node (ref "IC5") (pin "4") (pinfunction "SCK_4") (pintype "input"))
      (node (ref "IC7") (pin "3") (pinfunction "TX/SCL_3") (pintype "bidirectional"))
      (node (ref "IC8") (pin "4") (pinfunction "SCL_4") (pintype "bidirectional"))
      (node (ref "R1") (pin "2") (pinfunction "2_2") (pintype "passive"))
      (node (ref "U1") (pin "36") (pinfunction "IO22_36") (pintype "bidirectional"))
    )
    (net (code "10") (name "I2C_SDA") (class "Default")
      (node (ref "IC5") (pin "3") (pinfunction "SDI_3") (pintype "input"))
      (node (ref "IC7") (pin "4") (pinfunction "RX/SDA_4") (pintype "bidirectional"))
      (node (ref "IC8") (pin "6") (pinfunction "SDA_6") (pintype "bidirectional"))
      (node (ref "R2") (pin "2") (pinfunction "2_2") (pintype "passive"))
      (node (ref "U1") (pin "33") (pinfunction "IO21_33") (pintype "bidirectional"))
    )
    (net (code "11") (name "IO0") (class "Default")
      (node (ref "Q6") (pin "3") (pinfunction "C_3") (pintype "passive"))
      (node (ref "U1") (pin "25") (pinfunction "IO0_25") (pintype "bidirectional"))
    )
    (net (code "12") (name "LED_G") (class "Default")
      (node (ref "Q3") (pin "1") (pinfunction "G_1") (pintype "passive"))
      (node (ref "R22") (pin "1") (pinfunction "1_1") (pintype "passive"))
      (node (ref "U1") (pin "12") (pinfunction "IO27_12") (pintype "bidirectional"))
    )
    (net (code "13") (name "LED_R") (class "Default")
      (node (ref "Q1") (pin "1") (pinfunction "G_1") (pintype "passive"))
      (node (ref "R18") (pin "1") (pinfunction "1_1") (pintype "passive"))
      (node (ref "U1") (pin "10") (pinfunction "IO25_10") (pintype "bidirectional"))
    )
    (net (code "14") (name "LED_STATUS") (class "Default")
      (node (ref "R20") (pin "2") (pinfunction "2_2") (pintype "passive"))
      (node (ref "U1") (pin "26") (pinfunction "IO4_26") (pintype "bidirectional"))
    )
    (net (code "15") (name "LED_Y") (class "Default")
      (node (ref "Q2") (pin "1") (pinfunction "G_1") (pintype "passive"))
      (node (ref "R32") (pin "1") (pinfunction "1_1") (pintype "passive"))
      (node (ref "U1") (pin "11") (pinfunction "IO26_11") (pintype "bidirectional"))
    )
    (net (code "16") (name "MH_RXD") (class "Default")
      (node (ref "IC1") (pin "8") (pinfunction "RX_8") (pintype "bidirectional"))
      (node (ref "U1") (pin "28") (pinfunction "IO17_28") (pintype "bidirectional"))
    )
    (net (code "17") (name "MH_TXD") (class "Default")
      (node (ref "IC1") (pin "7") (pinfunction "TX_7") (pintype "bidirectional"))
      (node (ref "U1") (pin "27") (pinfunction "IO16_27") (pintype "bidirectional"))
    )
    (net (code "18") (name "MOSI") (class "Default")
      (node (ref "IC3") (pin "9") (pinfunction "I_9") (pintype "input"))
      (node (ref "U1") (pin "37") (pinfunction "IO23_37") (pintype "bidirectional"))
    )
    (net (code "19") (name "MOSI_5V") (class "Default")
      (node (ref "IC2") (pin "26") (pinfunction "DIO_26") (pintype "bidirectional"))
      (node (ref "IC3") (pin "8") (pinfunction "O_8") (pintype "tri_state"))
    )
    (net (code "20") (name "Net-(DISP1-A)") (class "Default")
      (node (ref "DISP1") (pin "8") (pinfunction "A_8") (pintype "bidirectional"))
      (node (ref "IC2") (pin "5") (pinfunction "SEG1_5") (pintype "bidirectional"))
    )
    (net (code "21") (name "Net-(DISP1-B)") (class "Default")
      (node (ref "DISP1") (pin "7") (pinfunction "B_7") (pintype "bidirectional"))
      (node (ref "IC2") (pin "6") (pinfunction "SEG2_6") (pintype "bidirectional"))
    )
    (net (code "22") (name "Net-(DISP1-C)") (class "Default")
      (node (ref "DISP1") (pin "12") (pinfunction "C_12") (pintype "bidirectional"))
      (node (ref "IC2") (pin "7") (pinfunction "SEG3_7") (pintype "bidirectional"))
    )
    (net (code "23") (name "Net-(DISP1-COM1)") (class "Default")
      (node (ref "DISP1") (pin "2") (pinfunction "COM1_2") (pintype "bidirectional"))
      (node (ref "IC2") (pin "24") (pinfunction "GRID1_24") (pintype "bidirectional"))
    )
    (net (code "24") (name "Net-(DISP1-COM2)") (class "Default")
      (node (ref "DISP1") (pin "3") (pinfunction "COM2_3") (pintype "bidirectional"))
      (node (ref "IC2") (pin "23") (pinfunction "GRID2_23") (pintype "bidirectional"))
    )
    (net (code "25") (name "Net-(DISP1-COM3)") (class "Default")
      (node (ref "DISP1") (pin "6") (pinfunction "COM3_6") (pintype "bidirectional"))
      (node (ref "IC2") (pin "22") (pinfunction "GRID3_22") (pintype "bidirectional"))
    )
    (net (code "26") (name "Net-(DISP1-COM4)") (class "Default")
      (node (ref "DISP1") (pin "10") (pinfunction "COM4_10") (pintype "bidirectional"))
      (node (ref "IC2") (pin "21") (pinfunction "GRID4_21") (pintype "bidirectional"))
    )
    (net (code "27") (name "Net-(DISP1-D)") (class "Default")
      (node (ref "DISP1") (pin "4") (pinfunction "D_4") (pintype "bidirectional"))
      (node (ref "IC2") (pin "8") (pinfunction "SEG4_8") (pintype "bidirectional"))
    )
    (net (code "28") (name "Net-(DISP1-DP)") (class "Default")
      (node (ref "DISP1") (pin "11") (pinfunction "DP_11") (pintype "bidirectional"))
      (node (ref "IC2") (pin "12") (pinfunction "SEG8_12") (pintype "bidirectional"))
    )
    (net (code "29") (name "Net-(DISP1-E)") (class "Default")
      (node (ref "DISP1") (pin "1") (pinfunction "E_1") (pintype "bidirectional"))
      (node (ref "IC2") (pin "9") (pinfunction "SEG5_9") (pintype "bidirectional"))
    )
    (net (code "30") (name "Net-(DISP1-F)") (class "Default")
      (node (ref "DISP1") (pin "9") (pinfunction "F_9") (pintype "bidirectional"))
      (node (ref "IC2") (pin "10") (pinfunction "SEG6_10") (pintype "bidirectional"))
    )
    (net (code "31") (name "Net-(DISP1-G)") (class "Default")
      (node (ref "DISP1") (pin "5") (pinfunction "G_5") (pintype "bidirectional"))
      (node (ref "IC2") (pin "11") (pinfunction "SEG7_11") (pintype "bidirectional"))
    )
    (net (code "32") (name "Net-(F1-Pad2)") (class "Default")
      (node (ref "F1") (pin "2") (pinfunction "2_2") (pintype "passive"))
      (node (ref "L1") (pin "1") (pinfunction "1_1") (pintype "passive"))
    )
    (net (code "33") (name "Net-(LED1-PadC)") (class "Default")
      (node (ref "LED1") (pin "C") (pinfunction "C_C") (pintype "passive"))
      (node (ref "LED2") (pin "A") (pinfunction "A_A") (pintype "passive"))
    )
    (net (code "34") (name "Net-(LED2-PadC)") (class "Default")
      (node (ref "LED2") (pin "C") (pinfunction "C_C") (pintype "passive"))
      (node (ref "LED4") (pin "C") (pinfunction "C_C") (pintype "passive"))
      (node (ref "R4") (pin "2") (pinfunction "2_2") (pintype "passive"))
    )
    (net (code "35") (name "Net-(LED3-PadC)") (class "Default")
      (node (ref "LED3") (pin "C") (pinfunction "C_C") (pintype "passive"))
      (node (ref "LED4") (pin "A") (pinfunction "A_A") (pintype "passive"))
    )
    (net (code "36") (name "Net-(LED5-PadC)") (class "Default")
      (node (ref "LED5") (pin "C") (pinfunction "C_C") (pintype "passive"))
      (node (ref "LED6") (pin "A") (pinfunction "A_A") (pintype "passive"))
    )
    (net (code "37") (name "Net-(LED6-PadC)") (class "Default")
      (node (ref "LED6") (pin "C") (pinfunction "C_C") (pintype "passive"))
      (node (ref "LED8") (pin "C") (pinfunction "C_C") (pintype "passive"))
      (node (ref "R6") (pin "2") (pinfunction "2_2") (pintype "passive"))
    )
    (net (code "38") (name "Net-(LED7-PadC)") (class "Default")
      (node (ref "LED7") (pin "C") (pinfunction "C_C") (pintype "passive"))
      (node (ref "LED8") (pin "A") (pinfunction "A_A") (pintype "passive"))
    )
    (net (code "39") (name "Net-(LED10-PadA)") (class "Default")
      (node (ref "LED10") (pin "A") (pinfunction "A_A") (pintype "passive"))
      (node (ref "LED9") (pin "C") (pinfunction "C_C") (pintype "passive"))
    )
    (net (code "40") (name "Net-(LED10-PadC)") (class "Default")
      (node (ref "LED10") (pin "C") (pinfunction "C_C") (pintype "passive"))
      (node (ref "LED12") (pin "C") (pinfunction "C_C") (pintype "passive"))
      (node (ref "R8") (pin "2") (pinfunction "2_2") (pintype "passive"))
    )
    (net (code "41") (name "Net-(LED11-PadC)") (class "Default")
      (node (ref "LED11") (pin "C") (pinfunction "C_C") (pintype "passive"))
      (node (ref "LED12") (pin "A") (pinfunction "A_A") (pintype "passive"))
    )
    (net (code "42") (name "Net-(LED13-PadC)") (class "Default")
      (node (ref "LED13") (pin "C") (pinfunction "C_C") (pintype "passive"))
      (node (ref "LED14") (pin "A") (pinfunction "A_A") (pintype "passive"))
    )
    (net (code "43") (name "Net-(LED14-PadC)") (class "Default")
      (node (ref "LED14") (pin "C") (pinfunction "C_C") (pintype "passive"))
      (node (ref "LED16") (pin "C") (pinfunction "C_C") (pintype "passive"))
      (node (ref "R10") (pin "2") (pinfunction "2_2") (pintype "passive"))
    )
    (net (code "44") (name "Net-(LED15-PadC)") (class "Default")
      (node (ref "LED15") (pin "C") (pinfunction "C_C") (pintype "passive"))
      (node (ref "LED16") (pin "A") (pinfunction "A_A") (pintype "passive"))
    )
    (net (code "45") (name "Net-(LED17-PadC)") (class "Default")
      (node (ref "LED17") (pin "C") (pinfunction "C_C") (pintype "passive"))
      (node (ref "LED18") (pin "A") (pinfunction "A_A") (pintype "passive"))
    )
    (net (code "46") (name "Net-(LED18-PadC)") (class "Default")
      (node (ref "LED18") (pin "C") (pinfunction "C_C") (pintype "passive"))
      (node (ref "LED20") (pin "C") (pinfunction "C_C") (pintype "passive"))
      (node (ref "R12") (pin "2") (pinfunction "2_2") (pintype "passive"))
    )
    (net (code "47") (name "Net-(LED19-PadC)") (class "Default")
      (node (ref "LED19") (pin "C") (pinfunction "C_C") (pintype "passive"))
      (node (ref "LED20") (pin "A") (pinfunction "A_A") (pintype "passive"))
    )
    (net (code "48") (name "Net-(LED21-PadC)") (class "Default")
      (node (ref "LED21") (pin "C") (pinfunction "C_C") (pintype "passive"))
      (node (ref "LED22") (pin "A") (pinfunction "A_A") (pintype "passive"))
    )
    (net (code "49") (name "Net-(LED22-PadC)") (class "Default")
      (node (ref "LED22") (pin "C") (pinfunction "C_C") (pintype "passive"))
      (node (ref "LED24") (pin "C") (pinfunction "C_C") (pintype "passive"))
      (node (ref "R14") (pin "2") (pinfunction "2_2") (pintype "passive"))
    )
    (net (code "50") (name "Net-(LED23-PadC)") (class "Default")
      (node (ref "LED23") (pin "C") (pinfunction "C_C") (pintype "passive"))
      (node (ref "LED24") (pin "A") (pinfunction "A_A") (pintype "passive"))
    )
    (net (code "51") (name "Net-(LED25-PadA)") (class "Default")
      (node (ref "LED25") (pin "A") (pinfunction "A_A") (pintype "passive"))
      (node (ref "R20") (pin "1") (pinfunction "1_1") (pintype "passive"))
    )
    (net (code "52") (name "Net-(LED27-PadC)") (class "Default")
      (node (ref "LED27") (pin "C") (pinfunction "C_C") (pintype "passive"))
      (node (ref "LED28") (pin "A") (pinfunction "A_A") (pintype "passive"))
    )
    (net (code "53") (name "Net-(LED28-PadC)") (class "Default")
      (node (ref "LED28") (pin "C") (pinfunction "C_C") (pintype "passive"))
      (node (ref "LED30") (pin "C") (pinfunction "C_C") (pintype "passive"))
      (node (ref "R19") (pin "2") (pinfunction "2_2") (pintype "passive"))
    )
    (net (code "54") (name "Net-(LED29-PadC)") (class "Default")
      (node (ref "LED29") (pin "C") (pinfunction "C_C") (pintype "passive"))
      (node (ref "LED30") (pin "A") (pinfunction "A_A") (pintype "passive"))
    )
    (net (code "55") (name "Net-(LED31-PadC)") (class "Default")
      (node (ref "LED31") (pin "C") (pinfunction "C_C") (pintype "passive"))
      (node (ref "LED32") (pin "A") (pinfunction "A_A") (pintype "passive"))
    )
    (net (code "56") (name "Net-(LED32-PadC)") (class "Default")
      (node (ref "LED32") (pin "C") (pinfunction "C_C") (pintype "passive"))
      (node (ref "LED34") (pin "C") (pinfunction "C_C") (pintype "passive"))
      (node (ref "R21") (pin "2") (pinfunction "2_2") (pintype "passive"))
    )
    (net (code "57") (name "Net-(LED33-PadC)") (class "Default")
      (node (ref "LED33") (pin "C") (pinfunction "C_C") (pintype "passive"))
      (node (ref "LED34") (pin "A") (pinfunction "A_A") (pintype "passive"))
    )
    (net (code "58") (name "Net-(LED35-PadC)") (class "Default")
      (node (ref "LED35") (pin "C") (pinfunction "C_C") (pintype "passive"))
      (node (ref "LED36") (pin "A") (pinfunction "A_A") (pintype "passive"))
    )
    (net (code "59") (name "Net-(LED36-PadC)") (class "Default")
      (node (ref "LED36") (pin "C") (pinfunction "C_C") (pintype "passive"))
      (node (ref "LED38") (pin "C") (pinfunction "C_C") (pintype "passive"))
      (node (ref "R23") (pin "2") (pinfunction "2_2") (pintype "passive"))
    )
    (net (code "60") (name "Net-(LED37-PadC)") (class "Default")
      (node (ref "LED37") (pin "C") (pinfunction "C_C") (pintype "passive"))
      (node (ref "LED38") (pin "A") (pinfunction "A_A") (pintype "passive"))
    )
    (net (code "61") (name "Net-(LED39-PadC)") (class "Default")
      (node (ref "LED39") (pin "C") (pinfunction "C_C") (pintype "passive"))
      (node (ref "LED40") (pin "A") (pinfunction "A_A") (pintype "passive"))
    )
    (net (code "62") (name "Net-(LED40-PadC)") (class "Default")
      (node (ref "LED40") (pin "C") (pinfunction "C_C") (pintype "passive"))
      (node (ref "LED42") (pin "C") (pinfunction "C_C") (pintype "passive"))
      (node (ref "R25") (pin "2") (pinfunction "2_2") (pintype "passive"))
    )
    (net (code "63") (name "Net-(LED41-PadC)") (class "Default")
      (node (ref "LED41") (pin "C") (pinfunction "C_C") (pintype "passive"))
      (node (ref "LED42") (pin "A") (pinfunction "A_A") (pintype "passive"))
    )
    (net (code "64") (name "Net-(LED43-PadC)") (class "Default")
      (node (ref "LED43") (pin "C") (pinfunction "C_C") (pintype "passive"))
      (node (ref "LED44") (pin "A") (pinfunction "A_A") (pintype "passive"))
    )
    (net (code "65") (name "Net-(LED44-PadC)") (class "Default")
      (node (ref "LED44") (pin "C") (pinfunction "C_C") (pintype "passive"))
      (node (ref "LED46") (pin "C") (pinfunction "C_C") (pintype "passive"))
      (node (ref "R27") (pin "2") (pinfunction "2_2") (pintype "passive"))
    )
    (net (code "66") (name "Net-(LED45-PadC)") (class "Default")
      (node (ref "LED45") (pin "C") (pinfunction "C_C") (pintype "passive"))
      (node (ref "LED46") (pin "A") (pinfunction "A_A") (pintype "passive"))
    )
    (net (code "67") (name "Net-(LED47-PadC)") (class "Default")
      (node (ref "LED47") (pin "C") (pinfunction "C_C") (pintype "passive"))
      (node (ref "LED48") (pin "A") (pinfunction "A_A") (pintype "passive"))
    )
    (net (code "68") (name "Net-(LED48-PadC)") (class "Default")
      (node (ref "LED48") (pin "C") (pinfunction "C_C") (pintype "passive"))
      (node (ref "LED50") (pin "C") (pinfunction "C_C") (pintype "passive"))
      (node (ref "R29") (pin "2") (pinfunction "2_2") (pintype "passive"))
    )
    (net (code "69") (name "Net-(LED49-PadC)") (class "Default")
      (node (ref "LED49") (pin "C") (pinfunction "C_C") (pintype "passive"))
      (node (ref "LED50") (pin "A") (pinfunction "A_A") (pintype "passive"))
    )
    (net (code "70") (name "Net-(LED53-PadC)") (class "Default")
      (node (ref "LED53") (pin "C") (pinfunction "C_C") (pintype "passive"))
      (node (ref "LED54") (pin "C") (pinfunction "C_C") (pintype "passive"))
      (node (ref "LED55") (pin "C") (pinfunction "C_C") (pintype "passive"))
      (node (ref "LED56") (pin "C") (pinfunction "C_C") (pintype "passive"))
      (node (ref "R5") (pin "2") (pinfunction "2_2") (pintype "passive"))
    )
    (net (code "71") (name "Net-(LED57-PadC)") (class "Default")
      (node (ref "LED57") (pin "C") (pinfunction "C_C") (pintype "passive"))
      (node (ref "LED58") (pin "C") (pinfunction "C_C") (pintype "passive"))
      (node (ref "LED59") (pin "C") (pinfunction "C_C") (pintype "passive"))
      (node (ref "LED60") (pin "C") (pinfunction "C_C") (pintype "passive"))
      (node (ref "R7") (pin "2") (pinfunction "2_2") (pintype "passive"))
    )
    (net (code "72") (name "Net-(LED61-PadC)") (class "Default")
      (node (ref "LED61") (pin "C") (pinfunction "C_C") (pintype "passive"))
      (node (ref "LED62") (pin "C") (pinfunction "C_C") (pintype "passive"))
      (node (ref "LED63") (pin "C") (pinfunction "C_C") (pintype "passive"))
      (node (ref "LED64") (pin "C") (pinfunction "C_C") (pintype "passive"))
      (node (ref "R9") (pin "2") (pinfunction "2_2") (pintype "passive"))
    )
    (net (code "73") (name "Net-(LED65-PadC)") (class "Default")
      (node (ref "LED65") (pin "C") (pinfunction "C_C") (pintype "passive"))
      (node (ref "LED66") (pin "C") (pinfunction "C_C") (pintype "passive"))
      (node (ref "LED67") (pin "C") (pinfunction "C_C") (pintype "passive"))
      (node (ref "LED68") (pin "C") (pinfunction "C_C") (pintype "passive"))
      (node (ref "R11") (pin "2") (pinfunction "2_2") (pintype "passive"))
    )
    (net (code "74") (name "Net-(LED69-PadC)") (class "Default")
      (node (ref "LED69") (pin "C") (pinfunction "C_C") (pintype "passive"))
      (node (ref "LED70") (pin "C") (pinfunction "C_C") (pintype "passive"))
      (node (ref "LED71") (pin "C") (pinfunction "C_C") (pintype "passive"))
      (node (ref "LED72") (pin "C") (pinfunction "C_C") (pintype "passive"))
      (node (ref "R13") (pin "2") (pinfunction "2_2") (pintype "passive"))
    )
    (net (code "75") (name "Net-(LED73-PadC)") (class "Default")
      (node (ref "LED73") (pin "C") (pinfunction "C_C") (pintype "passive"))
      (node (ref "LED74") (pin "C") (pinfunction "C_C") (pintype "passive"))
      (node (ref "LED75") (pin "C") (pinfunction "C_C") (pintype "passive"))
      (node (ref "LED76") (pin "C") (pinfunction "C_C") (pintype "passive"))
      (node (ref "R15") (pin "2") (pinfunction "2_2") (pintype "passive"))
    )
    (net (code "76") (name "Net-(Q1-D)") (class "Default")
      (node (ref "Q1") (pin "3") (pinfunction "D_3") (pintype "passive"))
      (node (ref "R10") (pin "1") (pinfunction "1_1") (pintype "passive"))
      (node (ref "R12") (pin "1") (pinfunction "1_1") (pintype "passive"))
      (node (ref "R14") (pin "1") (pinfunction "1_1") (pintype "passive"))
      (node (ref "R4") (pin "1") (pinfunction "1_1") (pintype "passive"))
      (node (ref "R6") (pin "1") (pinfunction "1_1") (pintype "passive"))
      (node (ref "R8") (pin "1") (pinfunction "1_1") (pintype "passive"))
    )
    (net (code "77") (name "Net-(Q2-D)") (class "Default")
      (node (ref "Q2") (pin "3") (pinfunction "D_3") (pintype "passive"))
      (node (ref "R19") (pin "1") (pinfunction "1_1") (pintype "passive"))
      (node (ref "R21") (pin "1") (pinfunction "1_1") (pintype "passive"))
      (node (ref "R23") (pin "1") (pinfunction "1_1") (pintype "passive"))
      (node (ref "R25") (pin "1") (pinfunction "1_1") (pintype "passive"))
      (node (ref "R27") (pin "1") (pinfunction "1_1") (pintype "passive"))
      (node (ref "R29") (pin "1") (pinfunction "1_1") (pintype "passive"))
    )
    (net (code "78") (name "Net-(Q3-D)") (class "Default")
      (node (ref "Q3") (pin "3") (pinfunction "D_3") (pintype "passive"))
      (node (ref "R11") (pin "1") (pinfunction "1_1") (pintype "passive"))
      (node (ref "R13") (pin "1") (pinfunction "1_1") (pintype "passive"))
      (node (ref "R15") (pin "1") (pinfunction "1_1") (pintype "passive"))
      (node (ref "R5") (pin "1") (pinfunction "1_1") (pintype "passive"))
      (node (ref "R7") (pin "1") (pinfunction "1_1") (pintype "passive"))
      (node (ref "R9") (pin "1") (pinfunction "1_1") (pintype "passive"))
    )
    (net (code "79") (name "Net-(Q4-D)") (class "Default")
      (node (ref "BZ2") (pin "-") (pinfunction "-_-") (pintype "passive"))
      (node (ref "Q4") (pin "3") (pinfunction "D_3") (pintype "passive"))
    )
    (net (code "80") (name "Net-(Q5-B)") (class "Default")
      (node (ref "Q5") (pin "1") (pinfunction "B_1") (pintype "passive"))
      (node (ref "R30") (pin "2") (pinfunction "2_2") (pintype "passive"))
    )
    (net (code "81") (name "Net-(Q6-B)") (class "Default")
      (node (ref "Q6") (pin "1") (pinfunction "B_1") (pintype "passive"))
      (node (ref "R31") (pin "2") (pinfunction "2_2") (pintype "passive"))
    )
    (net (code "82") (name "Net-(X1-CC1)") (class "Default")
      (node (ref "R16") (pin "2") (pinfunction "2_2") (pintype "passive"))
      (node (ref "X1") (pin "A5") (pinfunction "CC1_A5") (pintype "bidirectional"))
    )
    (net (code "83") (name "Net-(X1-CC2)") (class "Default")
      (node (ref "R3") (pin "2") (pinfunction "2_2") (pintype "passive"))
      (node (ref "X1") (pin "B5") (pinfunction "CC2_B5") (pintype "bidirectional"))
    )
    (net (code "84") (name "RTS") (class "Default")
      (node (ref "IC6") (pin "14") (pinfunction "RTS_14") (pintype "bidirectional"))
      (node (ref "Q5") (pin "2") (pinfunction "E_2") (pintype "passive"))
      (node (ref "R31") (pin "1") (pinfunction "1_1") (pintype "passive"))
    )
    (net (code "85") (name "SCK") (class "Default")
      (node (ref "IC3") (pin "5") (pinfunction "I_5") (pintype "input"))
      (node (ref "U1") (pin "30") (pinfunction "IO18_30") (pintype "bidirectional"))
    )
    (net (code "86") (name "SCK_5V") (class "Default")
      (node (ref "IC2") (pin "27") (pinfunction "CLK_27") (pintype "bidirectional"))
      (node (ref "IC3") (pin "6") (pinfunction "O_6") (pintype "tri_state"))
    )
    (net (code "87") (name "SWITCH_ALERT") (class "Default")
      (node (ref "S1") (pin "3") (pinfunction "P_3") (pintype "passive"))
      (node (ref "U1") (pin "14") (pinfunction "IO12_14") (pintype "bidirectional"))
    )
    (net (code "88") (name "SWITCH_BRIGHT") (class "Default")
      (node (ref "S2") (pin "3") (pinfunction "P_3") (pintype "passive"))
      (node (ref "U1") (pin "16") (pinfunction "IO13_16") (pintype "bidirectional"))
    )
    (net (code "89") (name "SWITCH_CAL") (class "Default")
      (node (ref "SW1") (pin "S1") (pinfunction "P_S1") (pintype "passive"))
      (node (ref "U1") (pin "9") (pinfunction "IO33_9") (pintype "bidirectional"))
    )
    (net (code "90") (name "USB_DM") (class "Default")
      (node (ref "D1") (pin "3") (pinfunction "2_3") (pintype "passive"))
      (node (ref "IC6") (pin "6") (pinfunction "D-_6") (pintype "bidirectional"))
      (node (ref "X1") (pin "A7") (pinfunction "DM_A7") (pintype "bidirectional"))
      (node (ref "X1") (pin "B7") (pinfunction "DM_B7") (pintype "bidirectional"))
    )
    (net (code "91") (name "USB_DP") (class "Default")
      (node (ref "D1") (pin "4") (pinfunction "3_4") (pintype "passive"))
      (node (ref "IC6") (pin "5") (pinfunction "D+_5") (pintype "bidirectional"))
      (node (ref "X1") (pin "A6") (pinfunction "DP_A6") (pintype "bidirectional"))
      (node (ref "X1") (pin "B6") (pinfunction "DP_B6") (pintype "bidirectional"))
    )
    (net (code "92") (name "USB_RXD") (class "Default")
      (node (ref "IC6") (pin "3") (pinfunction "RX_3") (pintype "bidirectional"))
      (node (ref "U1") (pin "35") (pinfunction "TXD_35") (pintype "bidirectional"))
    )
    (net (code "93") (name "USB_TXD") (class "Default")
      (node (ref "IC6") (pin "2") (pinfunction "TX_2") (pintype "bidirectional"))
      (node (ref "U1") (pin "34") (pinfunction "RXD_34") (pintype "bidirectional"))
    )
    (net (code "94") (name "VBUS") (class "Default")
      (node (ref "F1") (pin "1") (pinfunction "1_1") (pintype "passive"))
      (node (ref "X1") (pin "A4B9") (pinfunction "VBUS_A4B9") (pintype "bidirectional"))
      (node (ref "X1") (pin "B4A9") (pinfunction "VBUS_B4A9") (pintype "bidirectional"))
    )
    (net (code "95") (name "unconnected-(D1-4-Pad6)") (class "Default")
      (node (ref "D1") (pin "6") (pinfunction "4_6") (pintype "passive"))
    )
    (net (code "96") (name "unconnected-(D1-Pad1)") (class "Default")
      (node (ref "D1") (pin "1") (pinfunction "1_1") (pintype "passive"))
    )
    (net (code "97") (name "unconnected-(IC1-AOT-Pad3)") (class "Default")
      (node (ref "IC1") (pin "3") (pinfunction "AOT_3") (pintype "bidirectional"))
    )
    (net (code "98") (name "unconnected-(IC1-HD-Pad5)") (class "Default")
      (node (ref "IC1") (pin "5") (pinfunction "HD_5") (pintype "bidirectional"))
    )
    (net (code "99") (name "unconnected-(IC1-PWM-Pad4)") (class "Default")
      (node (ref "IC1") (pin "4") (pinfunction "PWM_4") (pintype "bidirectional"))
    )
    (net (code "100") (name "unconnected-(IC1-SR-Pad6)") (class "Default")
      (node (ref "IC1") (pin "6") (pinfunction "SR_6") (pintype "bidirectional"))
    )
    (net (code "101") (name "unconnected-(IC1-VO-Pad9)") (class "Default")
      (node (ref "IC1") (pin "9") (pinfunction "VO_9") (pintype "bidirectional"))
    )
    (net (code "102") (name "unconnected-(IC2-GRID5-Pad20)") (class "Default")
      (node (ref "IC2") (pin "20") (pinfunction "GRID5_20") (pintype "bidirectional"))
    )
    (net (code "103") (name "unconnected-(IC2-GRID6-Pad19)") (class "Default")
      (node (ref "IC2") (pin "19") (pinfunction "GRID6_19") (pintype "bidirectional"))
    )
    (net (code "104") (name "unconnected-(IC2-GRID7-Pad17)") (class "Default")
      (node (ref "IC2") (pin "17") (pinfunction "GRID7_17") (pintype "bidirectional"))
    )
    (net (code "105") (name "unconnected-(IC2-GRID8-Pad16)") (class "Default")
      (node (ref "IC2") (pin "16") (pinfunction "GRID8_16") (pintype "bidirectional"))
    )
    (net (code "106") (name "unconnected-(IC2-K1-Pad1)") (class "Default")
      (node (ref "IC2") (pin "1") (pinfunction "K1_1") (pintype "bidirectional"))
    )
    (net (code "107") (name "unconnected-(IC2-K2-Pad2)") (class "Default")
      (node (ref "IC2") (pin "2") (pinfunction "K2_2") (pintype "bidirectional"))
    )
    (net (code "108") (name "unconnected-(IC2-K3-Pad3)") (class "Default")
      (node (ref "IC2") (pin "3") (pinfunction "K3_3") (pintype "bidirectional"))
    )
    (net (code "109") (name "unconnected-(IC2-SEG9-Pad13)") (class "Default")
      (node (ref "IC2") (pin "13") (pinfunction "SEG9_13") (pintype "bidirectional"))
    )
    (net (code "110") (name "unconnected-(IC2-SEG10-Pad14)") (class "Default")
      (node (ref "IC2") (pin "14") (pinfunction "SEG10_14") (pintype "bidirectional"))
    )
    (net (code "111") (name "unconnected-(IC3D-O-Pad11)") (class "Default")
      (node (ref "IC3") (pin "11") (pinfunction "O_11") (pintype "tri_state"))
    )
    (net (code "112") (name "unconnected-(IC6-CTS-Pad9)") (class "Default")
      (node (ref "IC6") (pin "9") (pinfunction "CTS_9") (pintype "bidirectional"))
    )
    (net (code "113") (name "unconnected-(IC6-DCD-Pad12)") (class "Default")
      (node (ref "IC6") (pin "12") (pinfunction "DCD_12") (pintype "bidirectional"))
    )
    (net (code "114") (name "unconnected-(IC6-DSR-Pad10)") (class "Default")
      (node (ref "IC6") (pin "10") (pinfunction "DSR_10") (pintype "bidirectional"))
    )
    (net (code "115") (name "unconnected-(IC6-RI-Pad11)") (class "Default")
      (node (ref "IC6") (pin "11") (pinfunction "RI_11") (pintype "bidirectional"))
    )
    (net (code "116") (name "unconnected-(IC6-RS232-Pad15)") (class "Default")
      (node (ref "IC6") (pin "15") (pinfunction "RS232_15") (pintype "bidirectional"))
    )
    (net (code "117") (name "unconnected-(IC6-XI-Pad7)") (class "Default")
      (node (ref "IC6") (pin "7") (pinfunction "XI_7") (pintype "bidirectional"))
    )
    (net (code "118") (name "unconnected-(IC6-XO-Pad8)") (class "Default")
      (node (ref "IC6") (pin "8") (pinfunction "XO_8") (pintype "bidirectional"))
    )
    (net (code "119") (name "unconnected-(IC7-PWM-Pad6)") (class "Default")
      (node (ref "IC7") (pin "6") (pinfunction "PWM_6") (pintype "bidirectional"))
    )
    (net (code "120") (name "unconnected-(IC7-RDY-Pad5)") (class "Default")
      (node (ref "IC7") (pin "5") (pinfunction "RDY_5") (pintype "bidirectional"))
    )
    (net (code "121") (name "unconnected-(IC8-INT-Pad5)") (class "Default")
      (node (ref "IC8") (pin "5") (pinfunction "INT_5") (pintype "bidirectional"))
    )
    (net (code "122") (name "unconnected-(S1-P1-Pad4)") (class "Default")
      (node (ref "S1") (pin "4") (pinfunction "P1_4") (pintype "passive"))
    )
    (net (code "123") (name "unconnected-(S1-S1-Pad2)") (class "Default")
      (node (ref "S1") (pin "2") (pinfunction "S1_2") (pintype "passive"))
    )
    (net (code "124") (name "unconnected-(S2-P1-Pad4)") (class "Default")
      (node (ref "S2") (pin "4") (pinfunction "P1_4") (pintype "passive"))
    )
    (net (code "125") (name "unconnected-(S2-S1-Pad2)") (class "Default")
      (node (ref "S2") (pin "2") (pinfunction "S1_2") (pintype "passive"))
    )
    (net (code "126") (name "unconnected-(U1-IO2-Pad24)") (class "Default")
      (node (ref "U1") (pin "24") (pinfunction "IO2_24") (pintype "bidirectional"))
    )
    (net (code "127") (name "unconnected-(U1-IO14-Pad13)") (class "Default")
      (node (ref "U1") (pin "13") (pinfunction "IO14_13") (pintype "bidirectional"))
    )
    (net (code "128") (name "unconnected-(U1-IO15-Pad23)") (class "Default")
      (node (ref "U1") (pin "23") (pinfunction "IO15_23") (pintype "bidirectional"))
    )
    (net (code "129") (name "unconnected-(U1-IO19-Pad31)") (class "Default")
      (node (ref "U1") (pin "31") (pinfunction "IO19_31") (pintype "bidirectional"))
    )
    (net (code "130") (name "unconnected-(U1-IO20-Pad32)") (class "Default")
      (node (ref "U1") (pin "32") (pinfunction "IO20_32") (pintype "bidirectional"))
    )
    (net (code "131") (name "unconnected-(U1-IO34-Pad6)") (class "Default")
      (node (ref "U1") (pin "6") (pinfunction "IO34_6") (pintype "bidirectional"))
    )
    (net (code "132") (name "unconnected-(U1-IO35-Pad7)") (class "Default")
      (node (ref "U1") (pin "7") (pinfunction "IO35_7") (pintype "bidirectional"))
    )
    (net (code "133") (name "unconnected-(U1-SCK-Pad20)") (class "Default")
      (node (ref "U1") (pin "20") (pinfunction "SCK_20") (pintype "bidirectional"))
    )
    (net (code "134") (name "unconnected-(U1-SCS-Pad19)") (class "Default")
      (node (ref "U1") (pin "19") (pinfunction "SCS_19") (pintype "bidirectional"))
    )
    (net (code "135") (name "unconnected-(U1-SDI-Pad22)") (class "Default")
      (node (ref "U1") (pin "22") (pinfunction "SDI_22") (pintype "bidirectional"))
    )
    (net (code "136") (name "unconnected-(U1-SDO-Pad21)") (class "Default")
      (node (ref "U1") (pin "21") (pinfunction "SDO_21") (pintype "bidirectional"))
    )
    (net (code "137") (name "unconnected-(U1-SENSOR_VN-Pad5)") (class "Default")
      (node (ref "U1") (pin "5") (pinfunction "SENSOR_VN_5") (pintype "bidirectional"))
    )
    (net (code "138") (name "unconnected-(U1-SENSOR_VP-Pad4)") (class "Default")
      (node (ref "U1") (pin "4") (pinfunction "SENSOR_VP_4") (pintype "bidirectional"))
    )
    (net (code "139") (name "unconnected-(U1-SHD-Pad17)") (class "Default")
      (node (ref "U1") (pin "17") (pinfunction "SHD_17") (pintype "bidirectional"))
    )
    (net (code "140") (name "unconnected-(U1-SWP-Pad18)") (class "Default")
      (node (ref "U1") (pin "18") (pinfunction "SWP_18") (pintype "bidirectional"))
    )
    (net (code "141") (name "unconnected-(X1-SBU1-PadA8)") (class "Default")
      (node (ref "X1") (pin "A8") (pinfunction "SBU1_A8") (pintype "bidirectional"))
    )
    (net (code "142") (name "unconnected-(X1-SBU2-PadB8)") (class "Default")
      (node (ref "X1") (pin "B8") (pinfunction "SBU2_B8") (pintype "bidirectional"))
    )
  )
)
